# SDA381V7_B1.net
KiCad netlist of a schematic drawn in EAGLE
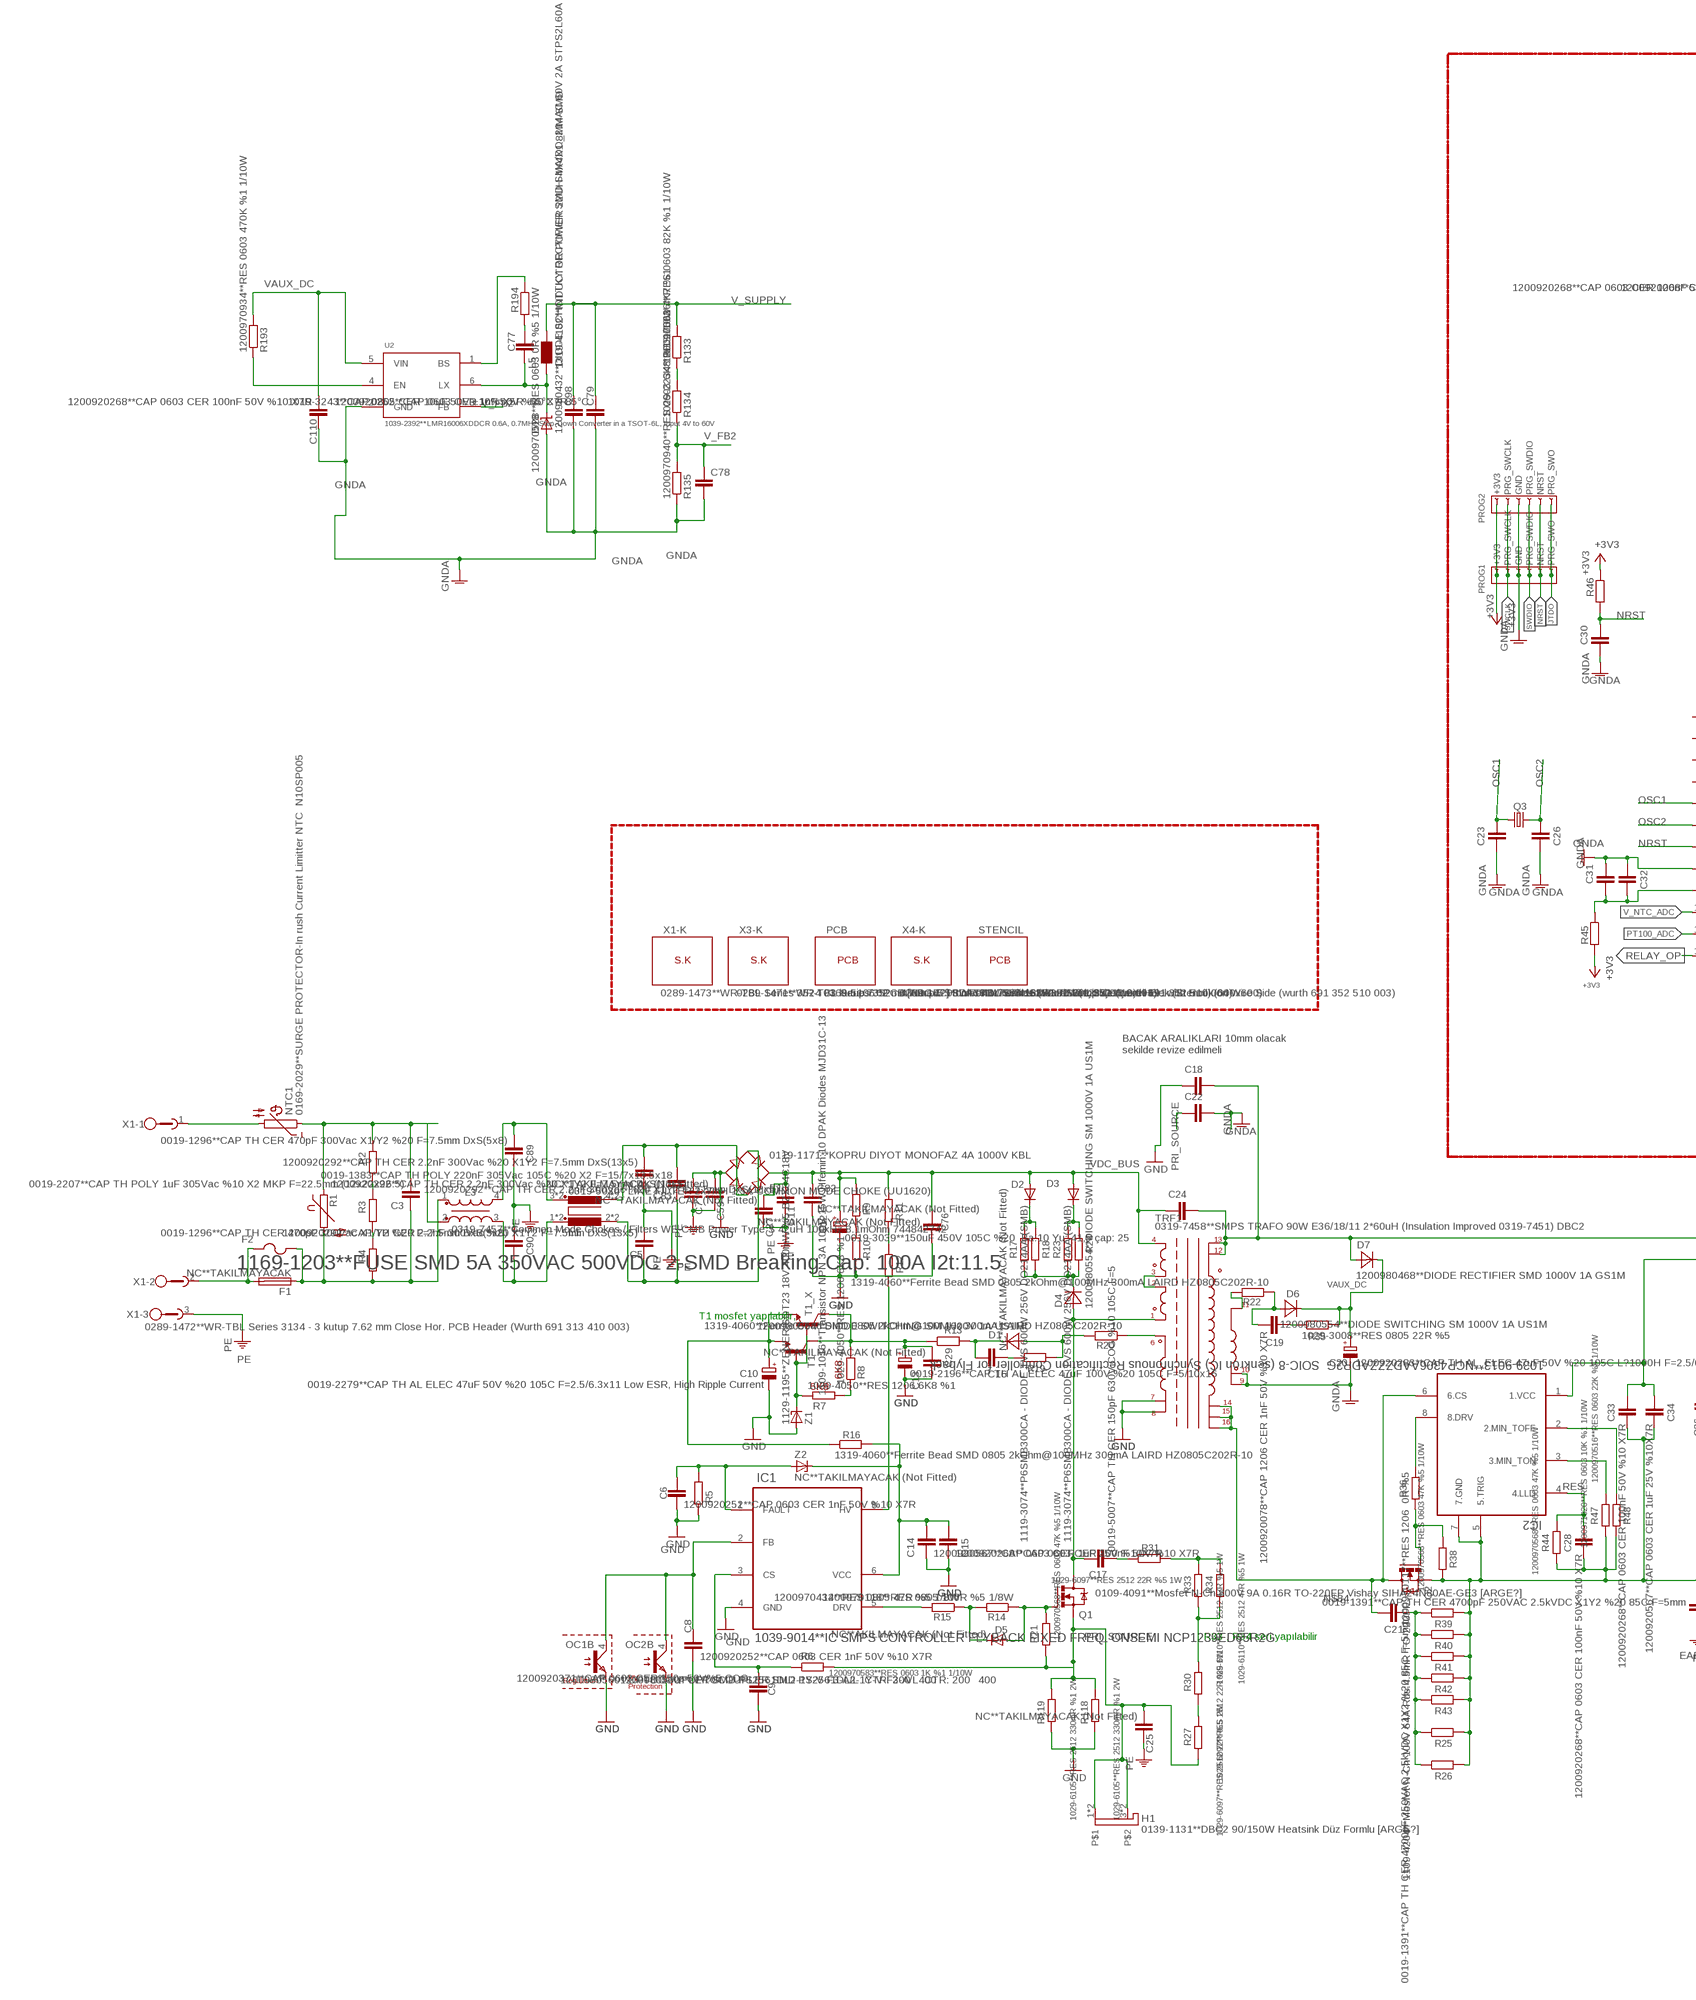
[diagram p0: schematic, sheet 1, part 1 of 2]
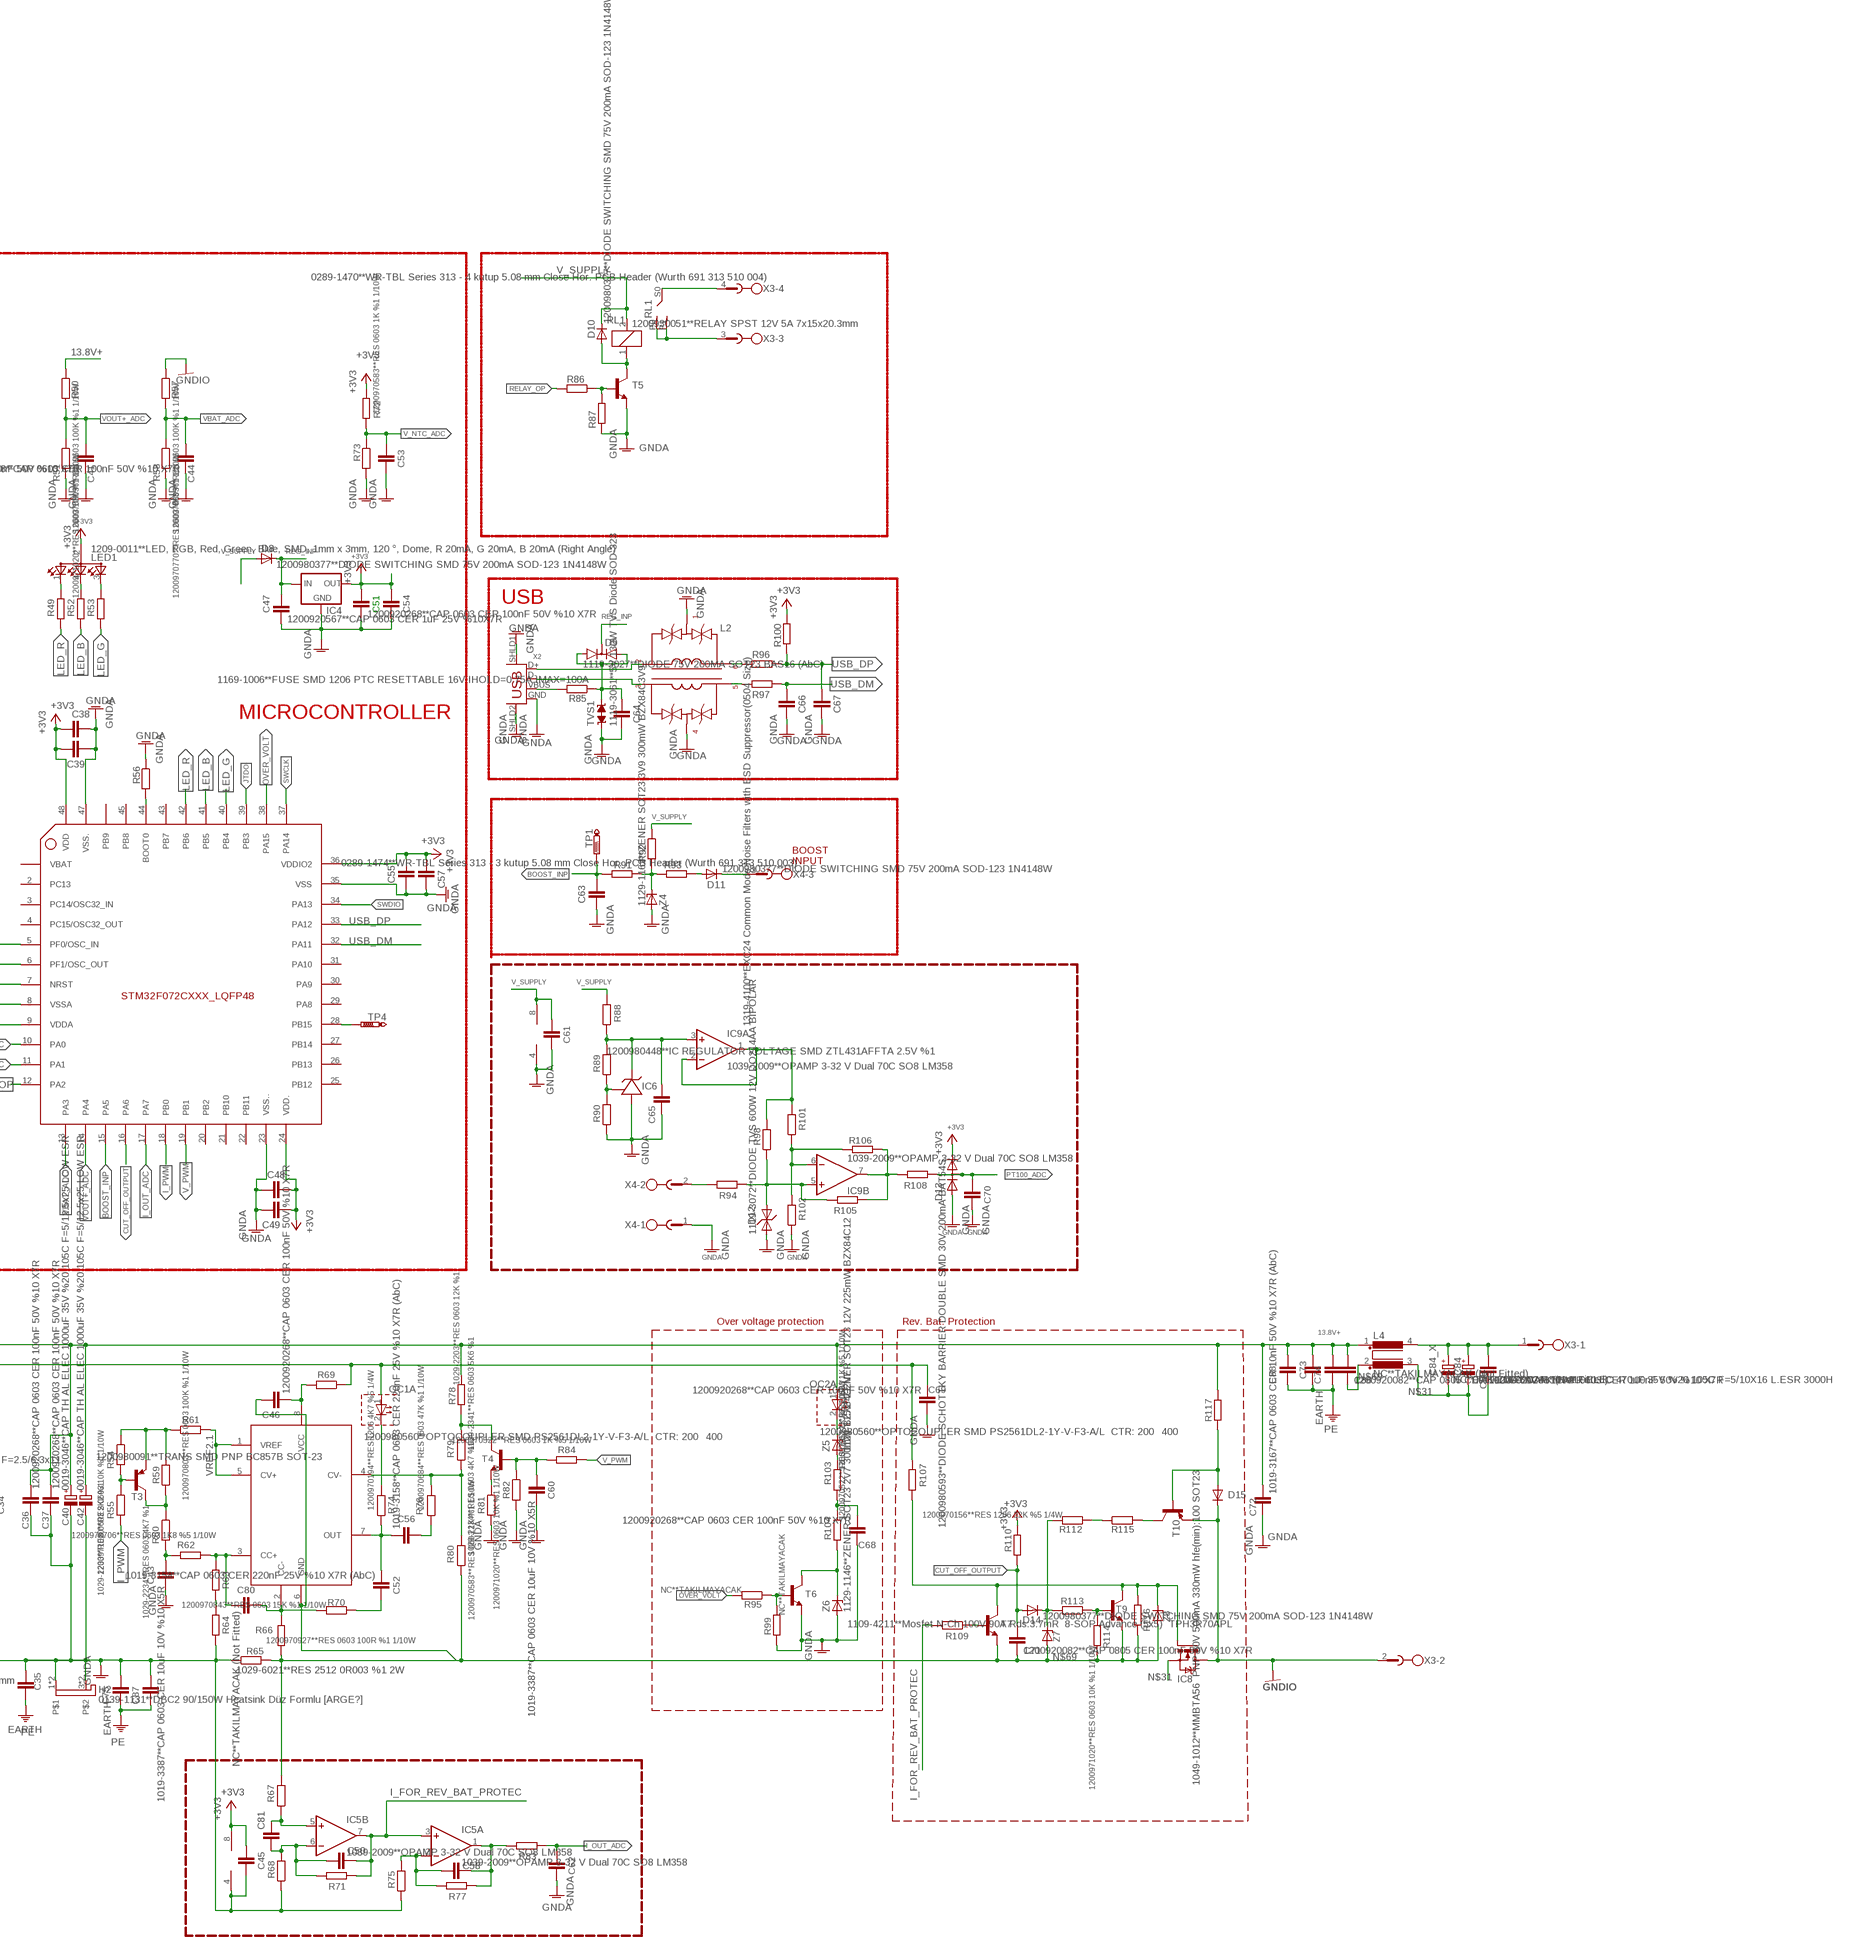
[diagram p1: schematic, sheet 1, part 2 of 2]

(export (version "E")
  (design (tool "Eeschema 10.0.6"))
  (components
    (comp (ref "B1")
      (value "0119-1171**KOPRU DIYOT MONOFAZ 4A 1000V KBL")
      (footprint "eagle-import:DıODE_BRIDGE_8A_DIK")
      (libsource (lib "eagle-import") (part "DıODE_BRIDGE_8A_DIK"))
    )
    (comp (ref "C3")
      (value "0019-2207**CAP TH POLY 1uF 305Vac %10 X2 MKP F=22.5mm (12x22x26.5)")
      (footprint "eagle-import:C275-113X316_&_C150-072X183_&_C225-113X268")
      (libsource (lib "eagle-import") (part "C275-113X316_&_C150-072X183_&_C225-113X268"))
    )
    (comp (ref "C4")
      (value "1200920292**CAP TH CER 2.2nF 300Vac %20 X1Y2 F=7.5mm DxS(13x5)")
      (footprint "eagle-import:C50-035X75")
      (libsource (lib "eagle-import") (part "C50-035X75"))
    )
    (comp (ref "C5")
      (value "1200920292**CAP TH CER 2.2nF 300Vac %20 X1Y2 F=7.5mm DxS(13x5)")
      (footprint "eagle-import:C50-035X75")
      (libsource (lib "eagle-import") (part "C50-035X75"))
    )
    (comp (ref "C6")
      (value "1200920252**CAP 0603 CER 1nF 50V %10 X7R")
      (footprint "eagle-import:C0603_ENKO")
      (libsource (lib "eagle-import") (part "C-EUC0603E"))
    )
    (comp (ref "C7")
      (value "1200920292**CAP TH CER 2.2nF 300Vac %20 X1Y2 F=7.5mm DxS(13x5)")
      (footprint "eagle-import:C50-035X75")
      (libsource (lib "eagle-import") (part "C50-035X75"))
    )
    (comp (ref "C8")
      (value "1200920252**CAP 0603 CER 1nF 50V %10 X7R")
      (footprint "eagle-import:C0603_ENKO")
      (libsource (lib "eagle-import") (part "C-EUC0603E"))
    )
    (comp (ref "C9")
      (value "1200920371**CAP 0603 CER 150p 50V%5 COG")
      (footprint "eagle-import:C0603_ENKO")
      (libsource (lib "eagle-import") (part "C-EUC0603E"))
    )
    (comp (ref "C10")
      (value "0019-2279**CAP TH AL ELEC 47uF 50V %20 105C F=2.5/6.3x11 Low ESR, High Ripple Current")
      (footprint "eagle-import:E2,5-7")
      (libsource (lib "eagle-import") (part "CPOL-EUE2.5-7"))
    )
    (comp (ref "C11")
      (value "1200920292**CAP TH CER 2.2nF 300Vac %20 X1Y2 F=7.5mm DxS(13x5)")
      (footprint "eagle-import:C50-035X75")
      (libsource (lib "eagle-import") (part "C50-035X75"))
    )
    (comp (ref "C12")
      (value "0019-3039**150uF 450V 105C %20 Ba:10 Yu: 41,5 çap: 25")
      (footprint "eagle-import:EB25D")
      (libsource (lib "eagle-import") (part "rcl_334_CPOL-EUE10-25"))
    )
    (comp (ref "C13")
      (value "0019-2196**CAP TH AL ELEC 47uF 100V %20 105C F=5/10x16")
      (footprint "eagle-import:E5-10,5")
      (libsource (lib "eagle-import") (part "CPOL-EUE5-10.5"))
    )
    (comp (ref "C14")
      (value "1200920567**CAP 0603 CER 1uF 25V %10X7R")
      (footprint "eagle-import:C0603_ENKO")
      (libsource (lib "eagle-import") (part "C-EUC0603E"))
    )
    (comp (ref "C15")
      (value "1200920268**CAP 0603 CER 100nF 50V %10 X7R")
      (footprint "eagle-import:C0603_ENKO")
      (libsource (lib "eagle-import") (part "C-EUC0603E"))
    )
    (comp (ref "C16")
      (value "NC**TAKILMAYACAK (Not Fitted)")
      (footprint "eagle-import:C1206_ENKO")
      (libsource (lib "eagle-import") (part "C-EUC1206E"))
    )
    (comp (ref "C17")
      (value "0019-5007**CAP TH CER 150pF 630V COG %10 105C F=5")
      (footprint "eagle-import:C075-32X103_C050-035X75")
      (libsource (lib "eagle-import") (part "C075-32X103/C050-035X75"))
    )
    (comp (ref "C18")
      (value "0019-1298**CAP TH CER 1nF 500Vac X1/Y1 %20 F=10mm DxS(5x9)")
      (footprint "eagle-import:C075-32X103_DEIF")
      (libsource (lib "eagle-import") (part "C075-32X103_DEIF"))
    )
    (comp (ref "C19")
      (value "1200920078**CAP 1206 CER 1nF 50V %10 X7R")
      (footprint "eagle-import:C1206_ENKO")
      (libsource (lib "eagle-import") (part "C-EUC1206E"))
    )
    (comp (ref "C20")
      (value "1200920283**CAP TH AL. ELEC 47uF 50V %20 105C L?1000H F=2.5/6.3x11")
      (footprint "eagle-import:E2,5-7")
      (libsource (lib "eagle-import") (part "rcl_334_CPOL-EUE2.5-7"))
    )
    (comp (ref "C21")
      (value "0019-1391**CAP TH CER 4700pF 250VAC 2.5kVDC X1Y2 %20 85C F=5mm")
      (footprint "eagle-import:C050-045X075")
      (libsource (lib "eagle-import") (part "C-EU050-045X075"))
    )
    (comp (ref "C22")
      (value "0019-1298**CAP TH CER 1nF 500Vac X1/Y1 %20 F=10mm DxS(5x9)")
      (footprint "eagle-import:C075-32X103_DEIF")
      (libsource (lib "eagle-import") (part "C075-32X103_DEIF"))
    )
    (comp (ref "C23")
      (value "1019-3352**CAP 0603 CER 22pF 50V %5 NPO")
      (footprint "eagle-import:C0603_ENKO")
      (libsource (lib "eagle-import") (part "C-EUC0603E"))
    )
    (comp (ref "C24")
      (value "0019-1299**CAP TH CER 2.2nF 500Vac X1/Y1 %20 F=10mm DxS(5x12)")
      (footprint "eagle-import:C075-32X103_DEIF")
      (libsource (lib "eagle-import") (part "C075-32X103_DEIF"))
    )
    (comp (ref "C25")
      (value "NC**TAKILMAYACAK (Not Fitted)")
      (footprint "eagle-import:C50-035X75")
      (libsource (lib "eagle-import") (part "C50-035X75"))
    )
    (comp (ref "C26")
      (value "1019-3352**CAP 0603 CER 22pF 50V %5 NPO")
      (footprint "eagle-import:C0603_ENKO")
      (libsource (lib "eagle-import") (part "C-EUC0603E"))
    )
    (comp (ref "C27")
      (value "NC**TAKILMAYACAK (Not Fitted)")
      (footprint "eagle-import:C50-035X75")
      (libsource (lib "eagle-import") (part "C50-035X75"))
    )
    (comp (ref "C28")
      (value "1200920268**CAP 0603 CER 100nF 50V %10 X7R")
      (footprint "eagle-import:C0603_ENKO")
      (libsource (lib "eagle-import") (part "C-EUC0603E"))
    )
    (comp (ref "C29")
      (value "NC**TAKILMAYACAK (Not Fitted)")
      (footprint "eagle-import:C1206_ENKO")
      (libsource (lib "eagle-import") (part "C-EUC1206E"))
    )
    (comp (ref "C30")
      (value "1200920268**CAP 0603 CER 100nF 50V %10 X7R")
      (footprint "eagle-import:C0603_ENKO")
      (libsource (lib "eagle-import") (part "C-EUC0603E"))
    )
    (comp (ref "C31")
      (value "1200920268**CAP 0603 CER 100nF 50V %10 X7R")
      (footprint "eagle-import:C0603_ENKO")
      (libsource (lib "eagle-import") (part "C-EUC0603E"))
    )
    (comp (ref "C32")
      (value "1019-3167**CAP 0603 CER 10nF 50V %10 X7R (AbC)")
      (footprint "eagle-import:C0603_ENKO")
      (libsource (lib "eagle-import") (part "C-EUC0603E"))
    )
    (comp (ref "C33")
      (value "1200920268**CAP 0603 CER 100nF 50V %10 X7R")
      (footprint "eagle-import:C0603_ENKO")
      (libsource (lib "eagle-import") (part "C-EUC0603E"))
    )
    (comp (ref "C34")
      (value "1200920567**CAP 0603 CER 1uF 25V %10X7R")
      (footprint "eagle-import:C0603_ENKO")
      (libsource (lib "eagle-import") (part "C-EUC0603E"))
    )
    (comp (ref "C35")
      (value "0019-1391**CAP TH CER 4700pF 250VAC 2.5kVDC X1Y2 %20 85C F=5mm")
      (footprint "eagle-import:C050-045X075")
      (libsource (lib "eagle-import") (part "C-EU050-045X075"))
    )
    (comp (ref "C36")
      (value "1200920268**CAP 0603 CER 100nF 50V %10 X7R")
      (footprint "eagle-import:C0603_ENKO")
      (libsource (lib "eagle-import") (part "C-EUC0603E"))
    )
    (comp (ref "C37")
      (value "1200920268**CAP 0603 CER 100nF 50V %10 X7R")
      (footprint "eagle-import:C0603_ENKO")
      (libsource (lib "eagle-import") (part "C-EUC0603E"))
    )
    (comp (ref "C38")
      (value "1200920268**CAP 0603 CER 100nF 50V %10 X7R")
      (footprint "eagle-import:C0603_ENKO")
      (libsource (lib "eagle-import") (part "C-EUC0603E"))
    )
    (comp (ref "C39")
      (value "1019-3167**CAP 0603 CER 10nF 50V %10 X7R (AbC)")
      (footprint "eagle-import:C0603_ENKO")
      (libsource (lib "eagle-import") (part "C-EUC0603E"))
    )
    (comp (ref "C40")
      (value "0019-3046**CAP TH AL ELEC 1000uF 35V %20 105C F=5/12.5x25 LOW ESR")
      (footprint "eagle-import:E5-13_E7,5-16")
      (libsource (lib "eagle-import") (part "E5-13/E7,5-16"))
    )
    (comp (ref "C41")
      (value "1200920268**CAP 0603 CER 100nF 50V %10 X7R")
      (footprint "eagle-import:C0603_ENKO")
      (libsource (lib "eagle-import") (part "C-EUC0603E"))
    )
    (comp (ref "C42")
      (value "0019-3046**CAP TH AL ELEC 1000uF 35V %20 105C F=5/12.5x25 LOW ESR")
      (footprint "eagle-import:E5-13")
      (libsource (lib "eagle-import") (part "CPOL-EUE5-13"))
    )
    (comp (ref "C43")
      (value "1019-3387**CAP 0603 CER 10uF 10V %10 X5R")
      (footprint "eagle-import:C0603_ENKO")
      (libsource (lib "eagle-import") (part "C-EUC0603E"))
    )
    (comp (ref "C44")
      (value "1200920268**CAP 0603 CER 100nF 50V %10 X7R")
      (footprint "eagle-import:C0603_ENKO")
      (libsource (lib "eagle-import") (part "C-EUC0603E"))
    )
    (comp (ref "C45")
      (value "1200920268**CAP 0603 CER 100nF 50V %10 X7R")
      (footprint "eagle-import:C0603_ENKO")
      (libsource (lib "eagle-import") (part "C-EUC0603E"))
    )
    (comp (ref "C46")
      (value "1200920268**CAP 0603 CER 100nF 50V %10 X7R")
      (footprint "eagle-import:C0603_ENKO")
      (libsource (lib "eagle-import") (part "C-EUC0603E"))
    )
    (comp (ref "C47")
      (value "1200920567**CAP 0603 CER 1uF 25V %10X7R")
      (footprint "eagle-import:C0603_ENKO")
      (libsource (lib "eagle-import") (part "C-EUC0603E"))
    )
    (comp (ref "C48")
      (value "1019-3167**CAP 0603 CER 10nF 50V %10 X7R (AbC)")
      (footprint "eagle-import:C0603_ENKO")
      (libsource (lib "eagle-import") (part "C-EUC0603E"))
    )
    (comp (ref "C49")
      (value "1200920268**CAP 0603 CER 100nF 50V %10 X7R")
      (footprint "eagle-import:C0603_ENKO")
      (libsource (lib "eagle-import") (part "C-EUC0603E"))
    )
    (comp (ref "C50")
      (value "NC**TAKILMAYACAK (Not Fitted)")
      (footprint "eagle-import:C0603_ENKO")
      (libsource (lib "eagle-import") (part "C-EUC0603E"))
    )
    (comp (ref "C51")
      (value "1200920268**CAP 0603 CER 100nF 50V %10 X7R")
      (footprint "eagle-import:C0603_ENKO")
      (libsource (lib "eagle-import") (part "C-EUC0603E"))
    )
    (comp (ref "C52")
      (value "1019-3158**CAP 0603 CER 220nF 25V %10 X7R (AbC)")
      (footprint "eagle-import:C0603_ENKO")
      (libsource (lib "eagle-import") (part "C-EUC0603E"))
    )
    (comp (ref "C53")
      (value "1200920268**CAP 0603 CER 100nF 50V %10 X7R")
      (footprint "eagle-import:C0603_ENKO")
      (libsource (lib "eagle-import") (part "C-EUC0603E"))
    )
    (comp (ref "C54")
      (value "1019-3301**CAP 0805 47uF 6.3V %20 X5R")
      (footprint "eagle-import:C0805_ENKO")
      (libsource (lib "eagle-import") (part "C-EUC0805E"))
    )
    (comp (ref "C55")
      (value "1019-3167**CAP 0603 CER 10nF 50V %10 X7R (AbC)")
      (footprint "eagle-import:C0603_ENKO")
      (libsource (lib "eagle-import") (part "C-EUC0603E"))
    )
    (comp (ref "C56")
      (value "1019-3158**CAP 0603 CER 220nF 25V %10 X7R (AbC)")
      (footprint "eagle-import:C0603_ENKO")
      (libsource (lib "eagle-import") (part "C-EUC0603E"))
    )
    (comp (ref "C57")
      (value "1200920268**CAP 0603 CER 100nF 50V %10 X7R")
      (footprint "eagle-import:C0603_ENKO")
      (libsource (lib "eagle-import") (part "C-EUC0603E"))
    )
    (comp (ref "C58")
      (value "1200920371**CAP 0603 CER 150p 50V%5 COG")
      (footprint "eagle-import:C0603_ENKO")
      (libsource (lib "eagle-import") (part "C-EUC0603E"))
    )
    (comp (ref "C59")
      (value "NC**TAKILMAYACAK (Not Fitted)")
      (footprint "eagle-import:C50-035X75")
      (libsource (lib "eagle-import") (part "C50-035X75"))
    )
    (comp (ref "C60")
      (value "1019-3387**CAP 0603 CER 10uF 10V %10 X5R")
      (footprint "eagle-import:C0603_ENKO")
      (libsource (lib "eagle-import") (part "C-EUC0603E"))
    )
    (comp (ref "C61")
      (value "1200920268**CAP 0603 CER 100nF 50V %10 X7R")
      (footprint "eagle-import:C0603_ENKO")
      (libsource (lib "eagle-import") (part "C-EUC0603E"))
    )
    (comp (ref "C62")
      (value "1200920268**CAP 0603 CER 100nF 50V %10 X7R")
      (footprint "eagle-import:C0603_ENKO")
      (libsource (lib "eagle-import") (part "C-EUC0603E"))
    )
    (comp (ref "C63")
      (value "1019-3167**CAP 0603 CER 10nF 50V %10 X7R (AbC)")
      (footprint "eagle-import:C0603_ENKO")
      (libsource (lib "eagle-import") (part "C-EUC0603E"))
    )
    (comp (ref "C64")
      (value "1200920268**CAP 0603 CER 100nF 50V %10 X7R")
      (footprint "eagle-import:C0603_ENKO")
      (libsource (lib "eagle-import") (part "C-EUC0603E"))
    )
    (comp (ref "C65")
      (value "1200920268**CAP 0603 CER 100nF 50V %10 X7R")
      (footprint "eagle-import:C0603_ENKO")
      (libsource (lib "eagle-import") (part "C-EUC0603E"))
    )
    (comp (ref "C66")
      (value "1019-3381**CAP 0603 CER 33pf 50V %5 NPO(COG)")
      (footprint "eagle-import:C0603_ENKO")
      (libsource (lib "eagle-import") (part "C-EUC0603E"))
    )
    (comp (ref "C67")
      (value "1019-3381**CAP 0603 CER 33pf 50V %5 NPO(COG)")
      (footprint "eagle-import:C0603_ENKO")
      (libsource (lib "eagle-import") (part "C-EUC0603E"))
    )
    (comp (ref "C68")
      (value "1200920268**CAP 0603 CER 100nF 50V %10 X7R")
      (footprint "eagle-import:C0603_ENKO")
      (libsource (lib "eagle-import") (part "C-EUC0603E"))
    )
    (comp (ref "C69")
      (value "1200920268**CAP 0603 CER 100nF 50V %10 X7R")
      (footprint "eagle-import:C0603_ENKO")
      (libsource (lib "eagle-import") (part "C-EUC0603E"))
    )
    (comp (ref "C70")
      (value "1200920268**CAP 0603 CER 100nF 50V %10 X7R")
      (footprint "eagle-import:C0603_ENKO")
      (libsource (lib "eagle-import") (part "C-EUC0603E"))
    )
    (comp (ref "C71")
      (value "1200920082**CAP 0805 CER 100nF 50V %10 X7R")
      (footprint "eagle-import:C0805_ENKO")
      (libsource (lib "eagle-import") (part "C-EUC0805E"))
    )
    (comp (ref "C72")
      (value "1019-3167**CAP 0603 CER 10nF 50V %10 X7R (AbC)")
      (footprint "eagle-import:C0603_ENKO")
      (libsource (lib "eagle-import") (part "C-EUC0603E"))
    )
    (comp (ref "C73")
      (value "0019-1391**CAP TH CER 4700pF 250VAC 2.5kVDC X1Y2 %20 85C F=5mm")
      (footprint "eagle-import:C050-035X075")
      (libsource (lib "eagle-import") (part "C-EU050-035X075"))
    )
    (comp (ref "C74")
      (value "0019-1391**CAP TH CER 4700pF 250VAC 2.5kVDC X1Y2 %20 85C F=5mm")
      (footprint "eagle-import:C075-32X103_DEIF")
      (libsource (lib "eagle-import") (part "C075-32X103_DEIF"))
    )
    (comp (ref "C75")
      (value "0019-1391**CAP TH CER 4700pF 250VAC 2.5kVDC X1Y2 %20 85C F=5mm")
      (footprint "eagle-import:C075-32X103_DEIF")
      (libsource (lib "eagle-import") (part "C075-32X103_DEIF"))
    )
    (comp (ref "C76")
      (value "NC**TAKILMAYACAK (Not Fitted)")
      (footprint "eagle-import:C065-052X106")
      (libsource (lib "eagle-import") (part "C065-052X106"))
    )
    (comp (ref "C77")
      (value "1200920268**CAP 0603 CER 100nF 50V %10 X7R")
      (footprint "eagle-import:C0603_ENKO")
      (libsource (lib "eagle-import") (part "C-EUC0603E"))
    )
    (comp (ref "C78")
      (value "1019-3352**CAP 0603 CER 22pF 50V %5 NPO")
      (footprint "eagle-import:C0603_ENKO")
      (libsource (lib "eagle-import") (part "C-EUC0603E"))
    )
    (comp (ref "C79")
      (value "1019-3243**CAP 0805 CER 10uF 50V ±10% X5R -55°C ~ 85°C")
      (footprint "eagle-import:C0805_ENKO")
      (libsource (lib "eagle-import") (part "C-EUC0805E"))
    )
    (comp (ref "C80")
      (value "NC**TAKILMAYACAK (Not Fitted)")
      (footprint "eagle-import:C0603_ENKO")
      (libsource (lib "eagle-import") (part "C-EUC0603E"))
    )
    (comp (ref "C81")
      (value "NC**TAKILMAYACAK (Not Fitted)")
      (footprint "eagle-import:C0603_ENKO")
      (libsource (lib "eagle-import") (part "C-EUC0603E"))
    )
    (comp (ref "C82")
      (value "NC**TAKILMAYACAK (Not Fitted)")
      (footprint "eagle-import:C150-091X182")
      (libsource (lib "eagle-import") (part "C-EU150-091X182"))
    )
    (comp (ref "C83")
      (value "0019-1383**CAP TH POLY 220nF 305Vac 105C %20 X2 F=15/7x13.5x18")
      (footprint "eagle-import:C150-091X182_C225-108X268")
      (libsource (lib "eagle-import") (part "C150-091X182_C225-108X268"))
    )
    (comp (ref "C84")
      (value "0019-7012**CAP TH AL. ELEC 470uF 35V %20 105C F=5/10X16 L.ESR 3000H")
      (footprint "eagle-import:E5-10,5")
      (libsource (lib "eagle-import") (part "CPOL-EUE5-10.5"))
    )
    (comp (ref "C84_X")
      (value "NC**TAKILMAYACAK (Not Fitted)")
      (footprint "eagle-import:E2,5-7")
      (libsource (lib "eagle-import") (part "CPOL-EUE2.5-7"))
    )
    (comp (ref "C85")
      (value "1200920268**CAP 0603 CER 100nF 50V %10 X7R")
      (footprint "eagle-import:C0603_ENKO")
      (libsource (lib "eagle-import") (part "C-EUC0603E"))
    )
    (comp (ref "C86")
      (value "1200920082**CAP 0805 CER 100nF 50V %10 X7R")
      (footprint "eagle-import:C0805_ENKO")
      (libsource (lib "eagle-import") (part "C-EUC0805E"))
    )
    (comp (ref "C87")
      (value "0019-3044**CAP TH CER 1nF 400VAC X1 %20 85C F=5 veya F=7.5 D=6.5")
      (footprint "eagle-import:C075-32X103_DEIF")
      (libsource (lib "eagle-import") (part "C075-32X103_DEIF"))
    )
    (comp (ref "C88")
      (value "0019-3044**CAP TH CER 1nF 400VAC X1 %20 85C F=5 veya F=7.5 D=6.5")
      (footprint "eagle-import:C075-32X103_DEIF")
      (libsource (lib "eagle-import") (part "C075-32X103_DEIF"))
    )
    (comp (ref "C89")
      (value "0019-1296**CAP TH CER 470pF 300Vac X1/Y2 %20 F=7.5mm DxS(5x8)")
      (footprint "eagle-import:C075-32X103_C050-035X75")
      (libsource (lib "eagle-import") (part "C075-32X103/C050-035X75"))
    )
    (comp (ref "C90")
      (value "0019-1296**CAP TH CER 470pF 300Vac X1/Y2 %20 F=7.5mm DxS(5x8)")
      (footprint "eagle-import:C075-32X103_C050-035X75")
      (libsource (lib "eagle-import") (part "C075-32X103/C050-035X75"))
    )
    (comp (ref "C98")
      (value "1200920252**CAP 0603 CER 1nF 50V %10 X7R")
      (footprint "eagle-import:C0603_ENKO")
      (libsource (lib "eagle-import") (part "C-EUC0603E"))
    )
    (comp (ref "C110")
      (value "1200920268**CAP 0603 CER 100nF 50V %10 X7R")
      (footprint "eagle-import:C0603_ENKO")
      (libsource (lib "eagle-import") (part "C-EUC0603E"))
    )
    (comp (ref "D1")
      (value "1200980554**DIODE SWITCHING SM 1000V 1A US1M")
      (footprint "eagle-import:M7_DC_DIYOT")
      (libsource (lib "eagle-import") (part "M7_DC_DIYOT"))
    )
    (comp (ref "D2")
      (value "1119-3074**P6SMB300CA - DIODE TVS 600W 256V DO214AA (SMB)")
      (footprint "eagle-import:SMB")
      (libsource (lib "eagle-import") (part "DIODE-SMB"))
    )
    (comp (ref "D3")
      (value "1119-3074**P6SMB300CA - DIODE TVS 600W 256V DO214AA (SMB)")
      (footprint "eagle-import:SMB")
      (libsource (lib "eagle-import") (part "DIODE-SMB"))
    )
    (comp (ref "D4")
      (value "1200980554**DIODE SWITCHING SM 1000V 1A US1M")
      (footprint "eagle-import:M7_DC_DIYOT")
      (libsource (lib "eagle-import") (part "M7_DC_DIYOT"))
    )
    (comp (ref "D5")
      (value "NC**AKILMAYACAK (Not Fitted)")
      (footprint "eagle-import:SOD123")
      (libsource (lib "eagle-import") (part "DIODE-SOD123"))
    )
    (comp (ref "D6")
      (value "1200980554**DIODE SWITCHING SM 1000V 1A US1M")
      (footprint "eagle-import:M7_DC_DIYOT")
      (libsource (lib "eagle-import") (part "M7_DC_DIYOT"))
    )
    (comp (ref "D7")
      (value "1200980468**DIODE RECTIFIER SMD 1000V 1A GS1M")
      (footprint "eagle-import:M7_DC_DIYOT")
      (libsource (lib "eagle-import") (part "M7_DC_DIYOT"))
    )
    (comp (ref "D8")
      (value "1200980377**DIODE SWITCHING SMD 75V 200mA SOD-123 1N4148W")
      (footprint "eagle-import:SOD123")
      (libsource (lib "eagle-import") (part "DIODE-SOD123"))
    )
    (comp (ref "D9")
      (value "1119-3027**DIODE 75V 200MA SOT23 BAS16 (AbC)")
      (footprint "eagle-import:SOT23")
      (libsource (lib "eagle-import") (part "DIODE-2AC|CASOT23"))
    )
    (comp (ref "D10")
      (value "1200980377**DIODE SWITCHING SMD 75V 200mA SOD-123 1N4148W")
      (footprint "eagle-import:SOD123")
      (libsource (lib "eagle-import") (part "DIODE-SOD123"))
    )
    (comp (ref "D11")
      (value "1200980377**DIODE SWITCHING SMD 75V 200mA SOD-123 1N4148W")
      (footprint "eagle-import:SOD123")
      (libsource (lib "eagle-import") (part "DIODE-SOD123"))
    )
    (comp (ref "D12")
      (value "1119-3072**DIODE TVS 600W 12V DO214AA BIPOLAR")
      (footprint "eagle-import:TRANSIL_SMB")
      (libsource (lib "eagle-import") (part "TRANSIL_SMB"))
    )
    (comp (ref "D13")
      (value "1200980593**DIODE SCHOTTKY BARRIER DOUBLE SMD 30V 200mA BAT54S")
      (footprint "eagle-import:SOT23")
      (libsource (lib "eagle-import") (part "BAV199"))
    )
    (comp (ref "D14")
      (value "1200980377**DIODE SWITCHING SMD 75V 200mA SOD-123 1N4148W")
      (footprint "eagle-import:SOD123")
      (libsource (lib "eagle-import") (part "DIODE-SOD123"))
    )
    (comp (ref "D15")
      (value "1200980377**DIODE SWITCHING SMD 75V 200mA SOD-123 1N4148W")
      (footprint "eagle-import:SOD123")
      (libsource (lib "eagle-import") (part "DIODE-SOD123"))
    )
    (comp (ref "D18")
      (value "1200980432**DIODE SCHOTTKY RECTIFIER SMD SMA/DO_214AC 60V 2A STPS2L60A")
      (footprint "eagle-import:SMA")
      (libsource (lib "eagle-import") (part "SD-SMA"))
    )
    (comp (ref "F1")
      (value "NC**TAKILMAYACAK")
      (footprint "eagle-import:SENS_FUSE")
      (libsource (lib "eagle-import") (part "SENS_FUSE"))
    )
    (comp (ref "F2")
      (value "1169-1203**FUSE SMD 5A 350VAC 500VDC 2-SMD Breaking Cap: 100A I2t:11.5")
      (footprint "eagle-import:FUSE_1350HV_EAT")
      (fields
        (field (name "MANUFACTURER_PART_NUMBER") "TR-1350HV5-R")
        (field (name "COPYRIGHT") "Copyright (C) 2025 Ultra Librarian. All rights reserved.")
      )
      (libsource (lib "eagle-import") (part "TR-1350HV5-RFUSE_1350HV_EAT"))
    )
    (comp (ref "H1")
      (value "0139-1131**DBC2 90/150W Heatsink Düz Formlu [ARGE?]")
      (footprint "eagle-import:DEIF_SOGUTUCU_2")
      (libsource (lib "eagle-import") (part "DEIF_SOGUTUCU_2"))
    )
    (comp (ref "H2")
      (value "0139-1131**DBC2 90/150W Heatsink Düz Formlu [ARGE?]")
      (footprint "eagle-import:DEIF_SOGUTUCU_2")
      (libsource (lib "eagle-import") (part "DEIF_SOGUTUCU_2"))
    )
    (comp (ref "IC1")
      (value "1039-9014**IC SMPS CONTROLLER FLYBACK FIXED FREQ. ONSEMI NCP1239ED65R2G")
      (footprint "eagle-import:NCP1239_SMPS_IC")
      (libsource (lib "eagle-import") (part "NCP1239_SMPS_IC"))
    )
    (comp (ref "IC2")
      (value "1039-9013**NCP4306AADZZZADR2G SOIC-8 (senkron IC) Synchronous Rectification Controller for Flyback")
      (footprint "eagle-import:NCP4306")
      (libsource (lib "eagle-import") (part "NCP4306"))
    )
    (comp (ref "IC3")
      (value "1039-2224**TSM1011ID SO-8 Constant Voltage and Constant Current Controller")
      (footprint "eagle-import:SO-8")
      (libsource (lib "eagle-import") (part "TSM1011"))
    )
    (comp (ref "IC4")
      (value "1039-3003**Voltage Regulator SOT-89 3.3V Diodes AP2204RA-3.3TRG1")
      (footprint "eagle-import:SOT89")
      (libsource (lib "eagle-import") (part "S-812XSGUP"))
    )
    (comp (ref "IC5")
      (value "1039-2009**OPAMP 3-32 V Dual 70C SO8 LM358")
      (footprint "eagle-import:SO08")
      (libsource (lib "eagle-import") (part "LM358D"))
    )
    (comp (ref "IC6")
      (value "1200980448**IC REGULATOR VOLTAGE SMD ZTL431AFFTA 2.5V %1")
      (footprint "eagle-import:TL431_SOT23F")
      (libsource (lib "eagle-import") (part "TL431_SOT23F"))
    )
    (comp (ref "IC8")
      (value "1109-4211**Mosfet N-Ch 100V 90A Rds:3.7mR 8-SOP Advance (5x5) TPH3R70APL")
      (footprint "eagle-import:TPH6R30ANL")
      (libsource (lib "eagle-import") (part "TPH6R30ANL"))
    )
    (comp (ref "IC9")
      (value "1039-2009**OPAMP 3-32 V Dual 70C SO8 LM358")
      (footprint "eagle-import:SO08")
      (libsource (lib "eagle-import") (part "LM358D"))
    )
    (comp (ref "L1")
      (value "0319-5030**LINE FILTER 2x7mH 1,5A COMMON MODE CHOKE (UU1620)")
      (footprint "eagle-import:UU1620_&_FWCMET24V")
      (libsource (lib "eagle-import") (part "UU1620_&_FWCMET24V"))
    )
    (comp (ref "L2")
      (value "1319-4100**EXC24 Common Mode Noise Filters with ESD Suppressor(0504 Size)")
      (footprint "eagle-import:EXC24CS_COMMON_MODE")
      (libsource (lib "eagle-import") (part "EXC24CS_COMMON_MODE"))
    )
    (comp (ref "L3")
      (value "0319-7457**Common Mode Chokes / Filters WE-CMB Power Type S 42uH 100kHz 8.1mOhm 744842742")
      (footprint "eagle-import:WE-CMB_NIZN_S")
      (libsource (lib "eagle-import") (part "WE-CMB_NIZN_S_744842742"))
    )
    (comp (ref "L4")
      (value "NC**TAKILMAYACAK (Not Fitted)")
      (footprint "eagle-import:CM2021Y330R-10")
      (libsource (lib "eagle-import") (part "CM2021Y330R-10"))
    )
    (comp (ref "L5")
      (value "1319-4102**INDUCTOR POWER 22UH 4X4X1.8MM SMD")
      (footprint "eagle-import:WE-PD2_5MM")
      (libsource (lib "eagle-import") (part "WE-PD2WE_PD2_5MM"))
    )
    (comp (ref "LED1")
      (value "1209-0011**LED, RGB, Red, Green, Blue, SMD, 1mm x 3mm, 120 °, Dome, R 20mA, G 20mA, B 20mA (Right Angle)")
      (footprint "eagle-import:KPFA-3010RGBC-11")
      (libsource (lib "eagle-import") (part "KPFA-3010RGBC-11"))
    )
    (comp (ref "NTC1")
      (value "0169-2029**SURGE PROTECTOR-In rush Current Limitter NTC N10SP005")
      (footprint "eagle-import:NTC_15R_2A_&_N15SP005-5")
      (libsource (lib "eagle-import") (part "NTC_15R_2A_&_N15SP005-5"))
    )
    (comp (ref "OC1")
      (value "1200980560**OPTOCOUPLER SMD PS2561DL2-1Y-V-F3-A/L  CTR: 200˜400")
      (footprint "eagle-import:PS2561DL2-1_OPTO1")
      (libsource (lib "eagle-import") (part "PS2561DL2-1_OPTO1"))
    )
    (comp (ref "OC2")
      (value "1200980560**OPTOCOUPLER SMD PS2561DL2-1Y-V-F3-A/L  CTR: 200˜400")
      (footprint "eagle-import:PS2561DL2-1_OPTO1")
      (libsource (lib "eagle-import") (part "PS2561DL2-1_OPTO1"))
    )
    (comp (ref "PCB")
      (value "0369-5106**PCB [ARGE?] SDA381V7CF416M3HFS2(123x113.2)")
      (footprint "eagle-import:PCB")
      (libsource (lib "eagle-import") (part "PCB"))
    )
    (comp (ref "PROG1")
      (value "NC**TAKILMAYACAK (Not Fitted)")
      (footprint "eagle-import:PROG_6PIN")
      (libsource (lib "eagle-import") (part "PROG_6PIN"))
    )
    (comp (ref "PROG2")
      (value "NC**TAKILMAYACAK (Not Fitted)")
      (footprint "eagle-import:PROG_6PIN")
      (libsource (lib "eagle-import") (part "PROG_6PIN"))
    )
    (comp (ref "Q1")
      (value "0109-4091**Mosfet N-Ch 800V 9A 0.16R TO-220FP Vishay SIHA24N80AE-GE3 [ARGE?]")
      (footprint "eagle-import:TO220BV")
      (libsource (lib "eagle-import") (part "STP5NA50"))
    )
    (comp (ref "Q2")
      (value "1109-4204**Mosfet N-Ch 100V 64A Rds:4.5mR TO-220FP")
      (footprint "eagle-import:TO220BV")
      (libsource (lib "eagle-import") (part "STP5NA50"))
    )
    (comp (ref "Q3")
      (value "1149-0006**HC49S SMD KRISTAL 8MHZ -40+85 20PF 50PPM FAT Y3MM")
      (footprint "eagle-import:HC49UP")
      (libsource (lib "eagle-import") (part "CRYSTALHC49UP"))
    )
    (comp (ref "R1")
      (value "0169-2013**Varistor 20mm 300V")
      (footprint "eagle-import:S20K40")
      (libsource (lib "eagle-import") (part "S20K40"))
    )
    (comp (ref "R2")
      (value "1200970587**RES 1206 470K %5 1/4W")
      (footprint "eagle-import:R1206_ENKO")
      (libsource (lib "eagle-import") (part "R-EU_R1206E"))
    )
    (comp (ref "R3")
      (value "1200970587**RES 1206 470K %5 1/4W")
      (footprint "eagle-import:R1206_ENKO")
      (libsource (lib "eagle-import") (part "R-EU_R1206E"))
    )
    (comp (ref "R4")
      (value "1200970587**RES 1206 470K %5 1/4W")
      (footprint "eagle-import:R1206_ENKO")
      (libsource (lib "eagle-import") (part "R-EU_R1206E"))
    )
    (comp (ref "R5")
      (value "1200970687**RES 0603 56K %1 1/10W")
      (footprint "eagle-import:R0603_ENKO")
      (libsource (lib "eagle-import") (part "R-EU_R0603E"))
    )
    (comp (ref "R6")
      (value "1200970583**RES 0603 1K %1 1/10W")
      (footprint "eagle-import:R0603_ENKO")
      (libsource (lib "eagle-import") (part "R-EU_R0603E"))
    )
    (comp (ref "R7")
      (value "1029-4050**RES 1206 6K8 %1")
      (footprint "eagle-import:R1206_ENKO")
      (libsource (lib "eagle-import") (part "R-EU_R1206E"))
    )
    (comp (ref "R8")
      (value "1029-4050**RES 1206 6K8 %1")
      (footprint "eagle-import:R1206_ENKO")
      (libsource (lib "eagle-import") (part "R-EU_R1206E"))
    )
    (comp (ref "R9")
      (value "1200970179**RES 1206 330K %5 1/4W")
      (footprint "eagle-import:R1206_ENKO")
      (libsource (lib "eagle-import") (part "R-EU_R1206E"))
    )
    (comp (ref "R10")
      (value "1200970179**RES 1206 330K %5 1/4W")
      (footprint "eagle-import:R1206_ENKO")
      (libsource (lib "eagle-import") (part "R-EU_R1206E"))
    )
    (comp (ref "R11")
      (value "1200970154**RES 1206 2K2 %5 1/4W")
      (footprint "eagle-import:R1206_ENKO")
      (libsource (lib "eagle-import") (part "R-EU_R1206E"))
    )
    (comp (ref "R12")
      (value "1200970154**RES 1206 2K2 %5 1/4W")
      (footprint "eagle-import:R1206_ENKO")
      (libsource (lib "eagle-import") (part "R-EU_R1206E"))
    )
    (comp (ref "R13")
      (value "1029-3146**RES 1206 7R68 %1")
      (footprint "eagle-import:R1206_ENKO")
      (libsource (lib "eagle-import") (part "R-EU_R1206E"))
    )
    (comp (ref "R14")
      (value "1200970118**RES 0805 100R %5 1/8W")
      (footprint "eagle-import:R0805_ENKO")
      (libsource (lib "eagle-import") (part "R-EU_R0805E"))
    )
    (comp (ref "R15")
      (value "1200970434**RES 0805 47R %5 1/8W")
      (footprint "eagle-import:R0805_ENKO")
      (libsource (lib "eagle-import") (part "R-EU_R0805E"))
    )
    (comp (ref "R16")
      (value "1319-4060**Ferrite Bead SMD 0805 2kOhm@100MHz 300mA LAIRD HZ0805C202R-10")
      (footprint "eagle-import:R0805_ENKO")
      (libsource (lib "eagle-import") (part "R-EU_R0805E"))
    )
    (comp (ref "R17")
      (value "1029-3146**RES 1206 7R68 %1")
      (footprint "eagle-import:R1206_ENKO")
      (libsource (lib "eagle-import") (part "R-EU_R1206E"))
    )
    (comp (ref "R18")
      (value "1029-3146**RES 1206 7R68 %1")
      (footprint "eagle-import:R1206_ENKO")
      (libsource (lib "eagle-import") (part "R-EU_R1206E"))
    )
    (comp (ref "R19")
      (value "NC**TAKILMAYACAK (Not Fitted)")
      (footprint "eagle-import:R1206_ENKO")
      (libsource (lib "eagle-import") (part "R-EU_R1206E"))
    )
    (comp (ref "R20")
      (value "1319-4060**Ferrite Bead SMD 0805 2kOhm@100MHz 300mA LAIRD HZ0805C202R-10")
      (footprint "eagle-import:R0805_ENKO")
      (libsource (lib "eagle-import") (part "R-EU_R0805E"))
    )
    (comp (ref "R21")
      (value "1200970568**RES 0603 47K %5 1/10W")
      (footprint "eagle-import:R0603_ENKO")
      (libsource (lib "eagle-import") (part "R-EU_R0603E"))
    )
    (comp (ref "R22")
      (value "1319-4060**Ferrite Bead SMD 0805 2kOhm@100MHz 300mA LAIRD HZ0805C202R-10")
      (footprint "eagle-import:R0805_ENKO")
      (libsource (lib "eagle-import") (part "R-EU_R0805E"))
    )
    (comp (ref "R23")
      (value "1029-3146**RES 1206 7R68 %1")
      (footprint "eagle-import:R1206_ENKO")
      (libsource (lib "eagle-import") (part "R-EU_R1206E"))
    )
    (comp (ref "R24")
      (value "1029-3146**RES 1206 7R68 %1")
      (footprint "eagle-import:R1206_ENKO")
      (libsource (lib "eagle-import") (part "R-EU_R1206E"))
    )
    (comp (ref "R25")
      (value "1200970119**RES 1206 100R %5 1/4W")
      (footprint "eagle-import:R1206_ENKO")
      (libsource (lib "eagle-import") (part "R-EU_R1206E"))
    )
    (comp (ref "R26")
      (value "1200970119**RES 1206 100R %5 1/4W")
      (footprint "eagle-import:R1206_ENKO")
      (libsource (lib "eagle-import") (part "R-EU_R1206E"))
    )
    (comp (ref "R27")
      (value "1029-6097**RES 2512 22R %5 1W")
      (footprint "eagle-import:R2512")
      (libsource (lib "eagle-import") (part "R-EU_R2512"))
    )
    (comp (ref "R30")
      (value "1029-6097**RES 2512 22R %5 1W")
      (footprint "eagle-import:R2512")
      (libsource (lib "eagle-import") (part "R-EU_R2512"))
    )
    (comp (ref "R31")
      (value "1029-6097**RES 2512 22R %5 1W")
      (footprint "eagle-import:R2512")
      (libsource (lib "eagle-import") (part "R-EU_R2512"))
    )
    (comp (ref "R33")
      (value "1029-6110**RES 2512 47R %5 1W")
      (footprint "eagle-import:R2512")
      (libsource (lib "eagle-import") (part "R-EU_R2512"))
    )
    (comp (ref "R34")
      (value "1029-6110**RES 2512 47R %5 1W")
      (footprint "eagle-import:R2512")
      (libsource (lib "eagle-import") (part "R-EU_R2512"))
    )
    (comp (ref "R35")
      (value "1029-3008**RES 0805 22R %5")
      (footprint "eagle-import:R0805_ENKO")
      (libsource (lib "eagle-import") (part "R-EU_R0805E"))
    )
    (comp (ref "R36")
      (value "1200970117**RES 1206 0R %5")
      (footprint "eagle-import:R1206_ENKO")
      (libsource (lib "eagle-import") (part "R-EU_R1206E"))
    )
    (comp (ref "R38")
      (value "1200970568**RES 0603 47K %5 1/10W")
      (footprint "eagle-import:R0603_ENKO")
      (libsource (lib "eagle-import") (part "R-EU_R0603E"))
    )
    (comp (ref "R39")
      (value "1200970119**RES 1206 100R %5 1/4W")
      (footprint "eagle-import:R1206_ENKO")
      (libsource (lib "eagle-import") (part "R-EU_R1206E"))
    )
    (comp (ref "R40")
      (value "1200970119**RES 1206 100R %5 1/4W")
      (footprint "eagle-import:R1206_ENKO")
      (libsource (lib "eagle-import") (part "R-EU_R1206E"))
    )
    (comp (ref "R41")
      (value "1200970119**RES 1206 100R %5 1/4W")
      (footprint "eagle-import:R1206_ENKO")
      (libsource (lib "eagle-import") (part "R-EU_R1206E"))
    )
    (comp (ref "R42")
      (value "1200970119**RES 1206 100R %5 1/4W")
      (footprint "eagle-import:R1206_ENKO")
      (libsource (lib "eagle-import") (part "R-EU_R1206E"))
    )
    (comp (ref "R43")
      (value "1200970554**RES 1206 56R %1 1/4W")
      (footprint "eagle-import:R1206_ENKO")
      (libsource (lib "eagle-import") (part "R-EU_R1206E"))
    )
    (comp (ref "R44")
      (value "1200970568**RES 0603 47K %5 1/10W")
      (footprint "eagle-import:R0603_ENKO")
      (libsource (lib "eagle-import") (part "R-EU_R0603E"))
    )
    (comp (ref "R45")
      (value "1319-4060**Ferrite Bead SMD 0805 2kOhm@100MHz 300mA LAIRD HZ0805C202R-10")
      (footprint "eagle-import:R0805_ENKO")
      (libsource (lib "eagle-import") (part "R-EU_R0805E"))
    )
    (comp (ref "R46")
      (value "1200971020**RES 0603 10K %1 1/10W")
      (footprint "eagle-import:R0603_ENKO")
      (libsource (lib "eagle-import") (part "R-EU_R0603E"))
    )
    (comp (ref "R47")
      (value "1200971020**RES 0603 10K %1 1/10W")
      (footprint "eagle-import:R0603_ENKO")
      (libsource (lib "eagle-import") (part "R-EU_R0603E"))
    )
    (comp (ref "R48")
      (value "1200970516**RES 0603 22K %5 1/10W")
      (footprint "eagle-import:R0603_ENKO")
      (libsource (lib "eagle-import") (part "R-EU_R0603E"))
    )
    (comp (ref "R49")
      (value "1029-2005**RES 0603 220R %1")
      (footprint "eagle-import:R0603_ENKO")
      (libsource (lib "eagle-import") (part "R-EU_R0603E"))
    )
    (comp (ref "R50")
      (value "1200970803**RES 0603 100K %1 1/10W")
      (footprint "eagle-import:R0603_ENKO")
      (libsource (lib "eagle-import") (part "R-EU_R0603E"))
    )
    (comp (ref "R51")
      (value "1200971020**RES 0603 10K %1 1/10W")
      (footprint "eagle-import:R0603_ENKO")
      (libsource (lib "eagle-import") (part "R-EU_R0603E"))
    )
    (comp (ref "R52")
      (value "1029-2005**RES 0603 220R %1")
      (footprint "eagle-import:R0603_ENKO")
      (libsource (lib "eagle-import") (part "R-EU_R0603E"))
    )
    (comp (ref "R53")
      (value "1029-2005**RES 0603 220R %1")
      (footprint "eagle-import:R0603_ENKO")
      (libsource (lib "eagle-import") (part "R-EU_R0603E"))
    )
    (comp (ref "R54")
      (value "1200971020**RES 0603 10K %1 1/10W")
      (footprint "eagle-import:R0603_ENKO")
      (libsource (lib "eagle-import") (part "R-EU_R0603E"))
    )
    (comp (ref "R55")
      (value "1029-2233**RES 0603 2K2 %1")
      (footprint "eagle-import:R0603_ENKO")
      (libsource (lib "eagle-import") (part "rcl_334_R-EU_R0603E"))
    )
    (comp (ref "R56")
      (value "1200970522**RES 0603 1K %5 1/10W")
      (footprint "eagle-import:R0603_ENKO")
      (libsource (lib "eagle-import") (part "R-EU_R0603E"))
    )
    (comp (ref "R57")
      (value "1200970803**RES 0603 100K %1 1/10W")
      (footprint "eagle-import:R0603_ENKO")
      (libsource (lib "eagle-import") (part "R-EU_R0603E"))
    )
    (comp (ref "R58")
      (value "1200970770**RES 0603 4K3 %1 1/10W")
      (footprint "eagle-import:R0603_ENKO")
      (libsource (lib "eagle-import") (part "R-EU_R0603E"))
    )
    (comp (ref "R59")
      (value "1200970803**RES 0603 100K %1 1/10W")
      (footprint "eagle-import:R0603_ENKO")
      (libsource (lib "eagle-import") (part "R-EU_R0603E"))
    )
    (comp (ref "R60")
      (value "1029-2234**RES 0603 4K7 %1")
      (footprint "eagle-import:R0603_ENKO")
      (libsource (lib "eagle-import") (part "R-EU_R0603E"))
    )
    (comp (ref "R61")
      (value "1200970583**RES 0603 1K %1 1/10W")
      (footprint "eagle-import:R0603_ENKO")
      (libsource (lib "eagle-import") (part "R-EU_R0603E"))
    )
    (comp (ref "R62")
      (value "1200970706**RES 0603 1K8 %5 1/10W")
      (footprint "eagle-import:R0603_ENKO")
      (libsource (lib "eagle-import") (part "R-EU_R0603E"))
    )
    (comp (ref "R63")
      (value "1029-2003**RES 0603 10R %1")
      (footprint "eagle-import:R0603_ENKO")
      (libsource (lib "eagle-import") (part "R-EU_R0603E"))
    )
    (comp (ref "R64")
      (value "1029-2006**RES 0603 47R %1")
      (footprint "eagle-import:R0603_ENKO")
      (libsource (lib "eagle-import") (part "R-EU_R0603E"))
    )
    (comp (ref "R65")
      (value "1029-6021**RES 2512 0R003 %1 2W")
      (footprint "eagle-import:R2512")
      (libsource (lib "eagle-import") (part "R-EU_R2512"))
    )
    (comp (ref "R66")
      (value "1200970927**RES 0603 100R %1 1/10W")
      (footprint "eagle-import:R0603_ENKO")
      (libsource (lib "eagle-import") (part "R-EU_R0603E"))
    )
    (comp (ref "R67")
      (value "1200970522**RES 0603 1K %5 1/10W")
      (footprint "eagle-import:R0603_ENKO")
      (libsource (lib "eagle-import") (part "R-EU_R0603E"))
    )
    (comp (ref "R68")
      (value "1200970522**RES 0603 1K %5 1/10W")
      (footprint "eagle-import:R0603_ENKO")
      (libsource (lib "eagle-import") (part "R-EU_R0603E"))
    )
    (comp (ref "R69")
      (value "1029-3008**RES 0805 22R %5")
      (footprint "eagle-import:R0805_ENKO")
      (libsource (lib "eagle-import") (part "R-EU_R0805E"))
    )
    (comp (ref "R70")
      (value "1200970843**RES 0603 15K %1 1/10W")
      (footprint "eagle-import:R0603_ENKO")
      (libsource (lib "eagle-import") (part "rcl_334_R-EU_R0603E"))
    )
    (comp (ref "R71")
      (value "1029-2234**RES 0603 4K7 %1")
      (footprint "eagle-import:R0603_ENKO")
      (libsource (lib "eagle-import") (part "R-EU_R0603E"))
    )
    (comp (ref "R72")
      (value "1200970583**RES 0603 1K %1 1/10W")
      (footprint "eagle-import:R0603_ENKO")
      (libsource (lib "eagle-import") (part "R-EU_R0603E"))
    )
    (comp (ref "R73")
      (value "1169-1001**TSM2A103F3951RZ THINKING 0805 10K NTC 125C")
      (footprint "eagle-import:R0805_ENKO")
      (libsource (lib "eagle-import") (part "R-EU_R0805E"))
    )
    (comp (ref "R74")
      (value "1200970194**RES 1206 4K7 %5 1/4W")
      (footprint "eagle-import:R1206_ENKO")
      (libsource (lib "eagle-import") (part "R-EU_R1206E"))
    )
    (comp (ref "R75")
      (value "1200970583**RES 0603 1K %1 1/10W")
      (footprint "eagle-import:R0603_ENKO")
      (libsource (lib "eagle-import") (part "R-EU_R0603E"))
    )
    (comp (ref "R76")
      (value "1200970684**RES 0603 47K %1 1/10W")
      (footprint "eagle-import:R0603_ENKO")
      (libsource (lib "eagle-import") (part "rcl_334_R-EU_R0603E"))
    )
    (comp (ref "R77")
      (value "1029-6089**RES 0603 6K8 %5")
      (footprint "eagle-import:R0603_ENKO")
      (libsource (lib "eagle-import") (part "R-EU_R0603E"))
    )
    (comp (ref "R78")
      (value "1029-2203**RES 0603 12K %1")
      (footprint "eagle-import:R0603_ENKO")
      (libsource (lib "eagle-import") (part "R-EU_R0603E"))
    )
    (comp (ref "R79")
      (value "1029-2341**RES 0603 5K6 %1")
      (footprint "eagle-import:R0603_ENKO")
      (libsource (lib "eagle-import") (part "rcl_334_R-EU_R0603E"))
    )
    (comp (ref "R80")
      (value "1029-2234**RES 0603 4K7 %1")
      (footprint "eagle-import:R0603_ENKO")
      (libsource (lib "eagle-import") (part "rcl_334_R-EU_R0603E"))
    )
    (comp (ref "R81")
      (value "1200970583**RES 0603 1K %1 1/10W")
      (footprint "eagle-import:R0603_ENKO")
      (libsource (lib "eagle-import") (part "R-EU_R0603E"))
    )
    (comp (ref "R82")
      (value "1200971020**RES 0603 10K %1 1/10W")
      (footprint "eagle-import:R0603_ENKO")
      (libsource (lib "eagle-import") (part "R-EU_R0603E"))
    )
    (comp (ref "R83")
      (value "1200970522**RES 0603 1K %5 1/10W")
      (footprint "eagle-import:R0603_ENKO")
      (libsource (lib "eagle-import") (part "R-EU_R0603E"))
    )
    (comp (ref "R84")
      (value "1200970522**RES 0603 1K %5 1/10W")
      (footprint "eagle-import:R0603_ENKO")
      (libsource (lib "eagle-import") (part "R-EU_R0603E"))
    )
    (comp (ref "R85")
      (value "1169-1006**FUSE SMD 1206 PTC RESETTABLE 16V IHOLD=0.75A IMAX=100A")
      (footprint "eagle-import:R1206_ENKO")
      (libsource (lib "eagle-import") (part "R-EU_R1206E"))
    )
    (comp (ref "R86")
      (value "1200970522**RES 0603 1K %5 1/10W")
      (footprint "eagle-import:R0603_ENKO")
      (libsource (lib "eagle-import") (part "R-EU_R0603E"))
    )
    (comp (ref "R87")
      (value "1200971020**RES 0603 10K %1 1/10W")
      (footprint "eagle-import:R0603_ENKO")
      (libsource (lib "eagle-import") (part "R-EU_R0603E"))
    )
    (comp (ref "R88")
      (value "1029-2234**RES 0603 4K7 %1")
      (footprint "eagle-import:R0603_ENKO")
      (libsource (lib "eagle-import") (part "R-EU_R0603E"))
    )
    (comp (ref "R89")
      (value "1200970583**RES 0603 1K %1 1/10W")
      (footprint "eagle-import:R0603_ENKO")
      (libsource (lib "eagle-import") (part "R-EU_R0603E"))
    )
    (comp (ref "R90")
      (value "1029-2231**RES 0603 1K8 %1")
      (footprint "eagle-import:R0603_ENKO")
      (libsource (lib "eagle-import") (part "R-EU_R0603E"))
    )
    (comp (ref "R91")
      (value "1200971020**RES 0603 10K %1 1/10W")
      (footprint "eagle-import:R0603_ENKO")
      (libsource (lib "eagle-import") (part "R-EU_R0603E"))
    )
    (comp (ref "R92")
      (value "1200970568**RES 0603 47K %5 1/10W")
      (footprint "eagle-import:R0603_ENKO")
      (libsource (lib "eagle-import") (part "R-EU_R0603E"))
    )
    (comp (ref "R93")
      (value "1409-0025**RES 0603 470R %5 1/16W")
      (footprint "eagle-import:R0603_ENKO")
      (libsource (lib "eagle-import") (part "R-EU_R0603E"))
    )
    (comp (ref "R94")
      (value "1029-6086**RES 0603 22R %1")
      (footprint "eagle-import:R0603_ENKO")
      (libsource (lib "eagle-import") (part "R-EU_R0603E"))
    )
    (comp (ref "R95")
      (value "NC**TAKILMAYACAK")
      (footprint "eagle-import:R0603_ENKO")
      (libsource (lib "eagle-import") (part "R-EU_R0603E"))
    )
    (comp (ref "R96")
      (value "1029-6086**RES 0603 22R %1")
      (footprint "eagle-import:R0603_ENKO")
      (libsource (lib "eagle-import") (part "R-EU_R0603E"))
    )
    (comp (ref "R97")
      (value "1029-6086**RES 0603 22R %1")
      (footprint "eagle-import:R0603_ENKO")
      (libsource (lib "eagle-import") (part "R-EU_R0603E"))
    )
    (comp (ref "R98")
      (value "1029-2234**RES 0603 4K7 %1")
      (footprint "eagle-import:R0603_ENKO")
      (libsource (lib "eagle-import") (part "R-EU_R0603E"))
    )
    (comp (ref "R99")
      (value "NC**TAKILMAYACAK")
      (footprint "eagle-import:R0603_ENKO")
      (libsource (lib "eagle-import") (part "R-EU_R0603E"))
    )
    (comp (ref "R100")
      (value "1200970852**RES 0603 1K5 %5 1/10W ( <-1029-3501 )")
      (footprint "eagle-import:R0603_ENKO")
      (libsource (lib "eagle-import") (part "R-EU_R0603E"))
    )
    (comp (ref "R101")
      (value "1200970684**RES 0603 47K %1 1/10W")
      (footprint "eagle-import:R0603_ENKO")
      (libsource (lib "eagle-import") (part "R-EU_R0603E"))
    )
    (comp (ref "R102")
      (value "1200970583**RES 0603 1K %1 1/10W")
      (footprint "eagle-import:R0603_ENKO")
      (libsource (lib "eagle-import") (part "R-EU_R0603E"))
    )
    (comp (ref "R103")
      (value "1200970522**RES 0603 1K %5 1/10W")
      (footprint "eagle-import:R0603_ENKO")
      (libsource (lib "eagle-import") (part "R-EU_R0603E"))
    )
    (comp (ref "R104")
      (value "1200970522**RES 0603 1K %5 1/10W")
      (footprint "eagle-import:R0603_ENKO")
      (libsource (lib "eagle-import") (part "R-EU_R0603E"))
    )
    (comp (ref "R105")
      (value "1029-2229**RES 0603 120K %1")
      (footprint "eagle-import:R0603_ENKO")
      (libsource (lib "eagle-import") (part "R-EU_R0603E"))
    )
    (comp (ref "R106")
      (value "1029-2219**RES 0603 30K %1")
      (footprint "eagle-import:R0603_ENKO")
      (libsource (lib "eagle-import") (part "R-EU_R0603E"))
    )
    (comp (ref "R107")
      (value "1200970515**RES 0603 100K %5 1/10W")
      (footprint "eagle-import:R0603_ENKO")
      (libsource (lib "eagle-import") (part "R-EU_R0603E"))
    )
    (comp (ref "R108")
      (value "1200970730**RES 0603 560R %1 1/10W")
      (footprint "eagle-import:R0603_ENKO")
      (libsource (lib "eagle-import") (part "R-EU_R0603E"))
    )
    (comp (ref "R109")
      (value "1200971020**RES 0603 10K %1 1/10W")
      (footprint "eagle-import:R0603_ENKO")
      (libsource (lib "eagle-import") (part "R-EU_R0603E"))
    )
    (comp (ref "R110")
      (value "1200970516**RES 0603 22K %5 1/10W")
      (footprint "eagle-import:R0603_ENKO")
      (libsource (lib "eagle-import") (part "R-EU_R0603E"))
    )
    (comp (ref "R112")
      (value "1200970156**RES 1206 22K %5 1/4W")
      (footprint "eagle-import:R1206_ENKO")
      (libsource (lib "eagle-import") (part "R-EU_R1206E"))
    )
    (comp (ref "R113")
      (value "1200970121**RES 0805 1K %5 1/8W")
      (footprint "eagle-import:R0805_ENKO")
      (libsource (lib "eagle-import") (part "R-EU_R0805E"))
    )
    (comp (ref "R114")
      (value "1200971020**RES 0603 10K %1 1/10W")
      (footprint "eagle-import:R0603_ENKO")
      (libsource (lib "eagle-import") (part "R-EU_R0603E"))
    )
    (comp (ref "R115")
      (value "1200970156**RES 1206 22K %5 1/4W")
      (footprint "eagle-import:R1206_ENKO")
      (libsource (lib "eagle-import") (part "R-EU_R1206E"))
    )
    (comp (ref "R116")
      (value "1200970585**RES 0603 1M %5 1/10W")
      (footprint "eagle-import:R0603_ENKO")
      (libsource (lib "eagle-import") (part "R-EU_R0603E"))
    )
    (comp (ref "R117")
      (value "1029-6015**RES 1206 56K %5")
      (footprint "eagle-import:R1206_ENKO")
      (libsource (lib "eagle-import") (part "R-EU_R1206E"))
    )
    (comp (ref "R118")
      (value "1029-6105**RES 2512 330mR %1 2W")
      (footprint "eagle-import:R2512")
      (libsource (lib "eagle-import") (part "R-EU_R2512"))
    )
    (comp (ref "R119")
      (value "1029-6105**RES 2512 330mR %1 2W")
      (footprint "eagle-import:R2512")
      (libsource (lib "eagle-import") (part "R-EU_R2512"))
    )
    (comp (ref "R133")
      (value "1200970626**RES 0603 82K %1 1/10W")
      (footprint "eagle-import:R0603_ENKO")
      (libsource (lib "eagle-import") (part "R-EU_R0603E"))
    )
    (comp (ref "R134")
      (value "1029-2234**RES 0603 4K7 %1")
      (footprint "eagle-import:R0603_ENKO")
      (libsource (lib "eagle-import") (part "R-EU_R0603E"))
    )
    (comp (ref "R135")
      (value "1200970940**RES 0603 6K8 %1 1/10W")
      (footprint "eagle-import:R0603_ENKO")
      (libsource (lib "eagle-import") (part "R-EU_R0603E"))
    )
    (comp (ref "R193")
      (value "1200970934**RES 0603 470K %1 1/10W")
      (footprint "eagle-import:R0603_ENKO")
      (libsource (lib "eagle-import") (part "R-EU_R0603E"))
    )
    (comp (ref "R194")
      (value "1200970528**RES 0603 0R %5 1/10W")
      (footprint "eagle-import:R0603_ENKO")
      (libsource (lib "eagle-import") (part "R-EU_R0603E"))
    )
    (comp (ref "RL1")
      (value "1200930051**RELAY SPST 12V 5A 7x15x20.3mm")
      (footprint "eagle-import:ALD1_AND_ALJ_RELAY")
      (libsource (lib "eagle-import") (part "ALD1_AND_ALJ_RELAY"))
    )
    (comp (ref "STENCIL")
      (value "041-7554**SDA381V7 için Çerçeveli Elek (Stencil) (600x600)")
      (footprint "eagle-import:PCB")
      (libsource (lib "eagle-import") (part "PCB"))
    )
    (comp (ref "T1")
      (value "1109-1016**Transistor NPN 3A 100V 15W Hfemin:10 DPAK Diodes MJD31C-13")
      (footprint "eagle-import:DPAK")
      (libsource (lib "eagle-import") (part "MJD31C"))
    )
    (comp (ref "T1_X")
      (value "NC**TAKILMAYACAK (Not Fitted)")
      (footprint "eagle-import:SOT23")
      (libsource (lib "eagle-import") (part "BC848SMDALT1"))
    )
    (comp (ref "T3")
      (value "1200980091**TRANS SMD PNP BC857B SOT-23")
      (footprint "eagle-import:SOT23-BEC")
      (libsource (lib "eagle-import") (part "-PNP-SOT23-BECBC856B"))
    )
    (comp (ref "T4")
      (value "1200980090**TRANS SMD NPN BC847B SOT-23")
      (footprint "eagle-import:SOT23")
      (libsource (lib "eagle-import") (part "BC848SMDALT1"))
    )
    (comp (ref "T5")
      (value "1200980090**TRANS SMD NPN BC847B SOT-23")
      (footprint "eagle-import:SOT23")
      (libsource (lib "eagle-import") (part "BC848SMDALT1"))
    )
    (comp (ref "T6")
      (value "NC**TAKILMAYACAK")
      (footprint "eagle-import:SOT23")
      (libsource (lib "eagle-import") (part "BC848SMDALT1"))
    )
    (comp (ref "T7")
      (value "1200980090**TRANS SMD NPN BC847B SOT-23")
      (footprint "eagle-import:SOT23")
      (libsource (lib "eagle-import") (part "BC848SMDALT1"))
    )
    (comp (ref "T9")
      (value "1200980090**TRANS SMD NPN BC847B SOT-23")
      (footprint "eagle-import:SOT23")
      (libsource (lib "eagle-import") (part "BC848SMDALT1"))
    )
    (comp (ref "T10")
      (value "1049-1012**MMBTA56 PNP 80V 500mA 330mW hfe(min):100 SOT23")
      (footprint "eagle-import:SOT23-BEC")
      (libsource (lib "eagle-import") (part "-PNP-SOT23-BECBC856B"))
    )
    (comp (ref "TP1")
      (value "PTR1TP20R")
      (footprint "eagle-import:TP20R")
      (libsource (lib "eagle-import") (part "PTR1TP20R"))
    )
    (comp (ref "TP4")
      (value "PTR1TP20R")
      (footprint "eagle-import:TP20R")
      (libsource (lib "eagle-import") (part "PTR1TP20R"))
    )
    (comp (ref "TRF1")
      (value "0319-7458**SMPS TRAFO 90W E36/18/11 2*60uH (Insulation Improved 0319-7451) DBC2")
      (footprint "eagle-import:DEIF_TRF")
      (libsource (lib "eagle-import") (part "DEIF_TRF"))
    )
    (comp (ref "TVS1")
      (value "1119-3061**5V 130W TVS Diode SOD-323")
      (footprint "eagle-import:SOD323")
      (libsource (lib "eagle-import") (part "TVS-BD-SOD323"))
    )
    (comp (ref "U1")
      (value "1039-2220**STM32F072C8T6 64K Flash USB, CAN")
      (footprint "eagle-import:STM32F072CXXX_LQFP48")
      (libsource (lib "eagle-import") (part "STM32F072CXXX_LQFP48"))
    )
    (comp (ref "U2")
      (value "1039-2392**LMR16006XDDCR 0.6A, 0.7MHz Step-Down Converter in a TSOT-6L, Input 4V to 60V")
      (footprint "eagle-import:AOZ1282CI-1")
      (libsource (lib "eagle-import") (part "AOZ1282CI-1"))
    )
    (comp (ref "X1")
      (value "0289-1472**WR-TBL Series 3134 - 3 kutup 7.62 mm Close Hor. PCB Header (Wurth 691 313 410 003)")
      (footprint "eagle-import:GMSTBA3")
      (fields (field (name "MF") "FARNELL") (field (name "MPN") "1757255"))
      (libsource (lib "eagle-import") (part "GMSTBA3"))
    )
    (comp (ref "X1-K")
      (value "0289-1473**WR-TBL Series 3524 - 3 kutup 7.62 mm Hor. w. Hook on Wire Side (Wurth 691 352 410 003)")
      (footprint "eagle-import:SOKET")
      (libsource (lib "eagle-import") (part "SOKET"))
    )
    (comp (ref "X2")
      (value "0309-1064**USB Type-B Mini Connector Horizantal")
      (footprint "eagle-import:USB_B(YATIK)")
      (libsource (lib "eagle-import") (part "USB_B(YATIK)"))
    )
    (comp (ref "X3")
      (value "0289-1470**WR-TBL Series 313 - 4 kutup 5.08 mm Close Hor. PCB Header (Wurth 691 313 510 004)")
      (footprint "eagle-import:MSTBA4")
      (fields (field (name "MF") "FARNELL") (field (name "MPN") "1757268"))
      (libsource (lib "eagle-import") (part "MSTBA4"))
    )
    (comp (ref "X3-K")
      (value "0289-1471**WR-TBL Series 352 - 4 kutup 5.08 mm Hor. with Hook on Wire Side (wurth 691 352 510 004)")
      (footprint "eagle-import:SOKET")
      (libsource (lib "eagle-import") (part "SOKET"))
    )
    (comp (ref "X4")
      (value "0289-1474**WR-TBL Series 313 - 3 kutup 5.08 mm Close Hor. PCB Header (Wurth 691 313 510 003)")
      (footprint "eagle-import:MSTBA3")
      (fields (field (name "MF") "FARNELL") (field (name "MPN") "1757255"))
      (libsource (lib "eagle-import") (part "MSTBA3"))
    )
    (comp (ref "X4-K")
      (value "0289-1475**WR-TBL Series 352 - 3 kutup 5.08 mm Hor. with Hook on Wire Side (wurth 691 352 510 003)")
      (footprint "eagle-import:SOKET")
      (libsource (lib "eagle-import") (part "SOKET"))
    )
    (comp (ref "Z1")
      (value "1129-1195**ZENER SOT23 18V 400mW %5 BZX84C18V")
      (footprint "eagle-import:SOT23")
      (libsource (lib "eagle-import") (part "ZENER-DIODESOT23"))
    )
    (comp (ref "Z2")
      (value "NC**TAKILMAYACAK (Not Fitted)")
      (footprint "eagle-import:SOT23")
      (libsource (lib "eagle-import") (part "ZENER-DIODESOT23"))
    )
    (comp (ref "Z4")
      (value "1129-1162**ZENER SOT23 3V9 300mW BZX84C3V9")
      (footprint "eagle-import:SOT23")
      (libsource (lib "eagle-import") (part "ZENER-DIODESOT23"))
    )
    (comp (ref "Z5")
      (value "1129-1151**ZENER SOT23 12V 225mW BZX84C12")
      (footprint "eagle-import:SOT23")
      (libsource (lib "eagle-import") (part "ZENER-DIODESOT23"))
    )
    (comp (ref "Z6")
      (value "1129-1146**ZENER SOT23 2V7 300mW BZX84C2V7")
      (footprint "eagle-import:SOT23")
      (libsource (lib "eagle-import") (part "ZENER-DIODESOT23"))
    )
    (comp (ref "Z7")
      (value "1129-1151**ZENER SOT23 12V 225mW BZX84C12")
      (footprint "eagle-import:SOT23")
      (libsource (lib "eagle-import") (part "ZENER-DIODESOT23"))
    )
    (comp (ref "Z8")
      (value "1129-1140**ZENER SOT23 5V1 0.4W BZX84C5V1")
      (footprint "eagle-import:SOT23")
      (libsource (lib "eagle-import") (part "ZENER-DIODESOT23"))
    )
  )
  (nets
    (net (code "1") (name "+3V3") (class "Default")
      (node (ref "C38") (pin "1") (pinfunction "1_1") (pintype "passive"))
      (node (ref "C39") (pin "1") (pinfunction "1_1") (pintype "passive"))
      (node (ref "C45") (pin "1") (pinfunction "1_1") (pintype "passive"))
      (node (ref "C48") (pin "1") (pinfunction "1_1") (pintype "passive"))
      (node (ref "C49") (pin "1") (pinfunction "1_1") (pintype "passive"))
      (node (ref "C51") (pin "1") (pinfunction "1_1") (pintype "passive"))
      (node (ref "C54") (pin "1") (pinfunction "1_1") (pintype "passive"))
      (node (ref "C55") (pin "1") (pinfunction "1_1") (pintype "passive"))
      (node (ref "C57") (pin "1") (pinfunction "1_1") (pintype "passive"))
      (node (ref "D13") (pin "2") (pinfunction "C_2") (pintype "passive"))
      (node (ref "IC4") (pin "3") (pinfunction "OUT_3") (pintype "passive"))
      (node (ref "IC5") (pin "8") (pinfunction "V+_8") (pintype "power_in"))
      (node (ref "LED1") (pin "2") (pinfunction "2_2") (pintype "passive"))
      (node (ref "PROG1") (pin "1") (pinfunction "+3V3_1") (pintype "passive"))
      (node (ref "PROG2") (pin "1") (pinfunction "+3V3_1") (pintype "passive"))
      (node (ref "R100") (pin "2") (pinfunction "2_2") (pintype "passive"))
      (node (ref "R110") (pin "2") (pinfunction "2_2") (pintype "passive"))
      (node (ref "R45") (pin "2") (pinfunction "2_2") (pintype "passive"))
      (node (ref "R46") (pin "1") (pinfunction "1_1") (pintype "passive"))
      (node (ref "R72") (pin "2") (pinfunction "2_2") (pintype "passive"))
      (node (ref "U1") (pin "24") (pinfunction "VDD._24") (pintype "bidirectional"))
      (node (ref "U1") (pin "36") (pinfunction "VDDIO2_36") (pintype "bidirectional"))
      (node (ref "U1") (pin "48") (pinfunction "VDD_48") (pintype "bidirectional"))
    )
    (net (code "2") (name "/13.8V+") (class "Default")
      (node (ref "C18") (pin "P$1") (pinfunction "1_P$1") (pintype "passive"))
      (node (ref "C24") (pin "P$1") (pinfunction "1_P$1") (pintype "passive"))
      (node (ref "C36") (pin "1") (pinfunction "1_1") (pintype "passive"))
      (node (ref "C37") (pin "1") (pinfunction "1_1") (pintype "passive"))
      (node (ref "C40") (pin "+") (pinfunction "+_+") (pintype "passive"))
      (node (ref "C40") (pin "+1") (pinfunction "+_+1") (pintype "passive"))
      (node (ref "C42") (pin "+") (pinfunction "+_+") (pintype "passive"))
      (node (ref "C72") (pin "2") (pinfunction "2_2") (pintype "passive"))
      (node (ref "C73") (pin "1") (pinfunction "1_1") (pintype "passive"))
      (node (ref "C74") (pin "P$1") (pinfunction "1_P$1") (pintype "passive"))
      (node (ref "C86") (pin "1") (pinfunction "1_1") (pintype "passive"))
      (node (ref "C88") (pin "P$1") (pinfunction "1_P$1") (pintype "passive"))
      (node (ref "D7") (pin "A") (pinfunction "A_A") (pintype "passive"))
      (node (ref "L4") (pin "1") (pinfunction "1_1") (pintype "passive"))
      (node (ref "OC2") (pin "1") (pinfunction "1_1") (pintype "passive"))
      (node (ref "R117") (pin "1") (pinfunction "1_1") (pintype "passive"))
      (node (ref "R50") (pin "1") (pinfunction "1_1") (pintype "passive"))
      (node (ref "R78") (pin "2") (pinfunction "2_2") (pintype "passive"))
      (node (ref "TRF1") (pin "10") (pinfunction "13_10") (pintype "passive"))
      (node (ref "TRF1") (pin "21") (pinfunction "13_21") (pintype "passive"))
      (node (ref "TRF1") (pin "22") (pinfunction "12_22") (pintype "passive"))
      (node (ref "TRF1") (pin "29") (pinfunction "12_29") (pintype "passive"))
      (node (ref "TRF1") (pin "30") (pinfunction "13_30") (pintype "passive"))
      (node (ref "TRF1") (pin "43") (pinfunction "12_43") (pintype "passive"))
      (node (ref "TRF1") (pin "44") (pinfunction "13_44") (pintype "passive"))
      (node (ref "TRF1") (pin "9") (pinfunction "12_9") (pintype "passive"))
    )
    (net (code "3") (name "/I_FOR_REV_BAT_PROTEC") (class "Default")
      (node (ref "C50") (pin "2") (pinfunction "2_2") (pintype "passive"))
      (node (ref "IC5") (pin "3") (pinfunction "+IN_3") (pintype "input"))
      (node (ref "IC5") (pin "7") (pinfunction "OUT_7") (pintype "output"))
      (node (ref "R109") (pin "2") (pinfunction "2_2") (pintype "passive"))
      (node (ref "R71") (pin "2") (pinfunction "2_2") (pintype "passive"))
    )
    (net (code "4") (name "/N$31") (class "Default")
      (node (ref "C84") (pin "-") (pinfunction "-_-") (pintype "passive"))
      (node (ref "C84_X") (pin "-") (pinfunction "-_-") (pintype "passive"))
      (node (ref "C85") (pin "2") (pinfunction "2_2") (pintype "passive"))
      (node (ref "IC8") (pin "S") (pinfunction "S123_S") (pintype "passive"))
      (node (ref "IC8") (pin "S1") (pinfunction "S123_S1") (pintype "passive"))
      (node (ref "IC8") (pin "S2") (pinfunction "S123_S2") (pintype "passive"))
      (node (ref "L4") (pin "3") (pinfunction "3_3") (pintype "passive"))
    )
    (net (code "5") (name "/N$69") (class "Default")
      (node (ref "C46") (pin "1") (pinfunction "1_1") (pintype "passive"))
      (node (ref "C71") (pin "2") (pinfunction "2_2") (pintype "passive"))
      (node (ref "C86") (pin "2") (pinfunction "2_2") (pintype "passive"))
      (node (ref "IC3") (pin "6") (pinfunction "GND_6") (pintype "power_in"))
      (node (ref "L4") (pin "2") (pinfunction "2_2") (pintype "passive"))
      (node (ref "R114") (pin "2") (pinfunction "2_2") (pintype "passive"))
      (node (ref "R116") (pin "1") (pinfunction "1_1") (pintype "passive"))
      (node (ref "R65") (pin "2") (pinfunction "2_2") (pintype "passive"))
      (node (ref "R66") (pin "2") (pinfunction "2_2") (pintype "passive"))
      (node (ref "R67") (pin "2") (pinfunction "2_2") (pintype "passive"))
      (node (ref "R80") (pin "1") (pinfunction "1_1") (pintype "passive"))
      (node (ref "T7") (pin "2") (pinfunction "E_2") (pintype "passive"))
      (node (ref "T9") (pin "2") (pinfunction "E_2") (pintype "passive"))
      (node (ref "Z7") (pin "1") (pinfunction "A_1") (pintype "passive"))
      (node (ref "Z8") (pin "1") (pinfunction "A_1") (pintype "passive"))
    )
    (net (code "6") (name "/N$84") (class "Default")
      (node (ref "C21") (pin "1") (pinfunction "1_1") (pintype "passive"))
      (node (ref "IC2") (pin "6") (pinfunction "6.CS_6") (pintype "input"))
      (node (ref "Q2") (pin "D") (pinfunction "D_D") (pintype "passive"))
      (node (ref "TRF1") (pin "11") (pinfunction "14_11") (pintype "passive"))
      (node (ref "TRF1") (pin "12") (pinfunction "15_12") (pintype "passive"))
      (node (ref "TRF1") (pin "13") (pinfunction "16_13") (pintype "passive"))
      (node (ref "TRF1") (pin "19") (pinfunction "15_19") (pintype "passive"))
      (node (ref "TRF1") (pin "20") (pinfunction "14_20") (pintype "passive"))
      (node (ref "TRF1") (pin "25") (pinfunction "16_25") (pintype "passive"))
      (node (ref "TRF1") (pin "31") (pinfunction "14_31") (pintype "passive"))
      (node (ref "TRF1") (pin "32") (pinfunction "15_32") (pintype "passive"))
      (node (ref "TRF1") (pin "38") (pinfunction "16_38") (pintype "passive"))
      (node (ref "TRF1") (pin "45") (pinfunction "14_45") (pintype "passive"))
      (node (ref "TRF1") (pin "46") (pinfunction "15_46") (pintype "passive"))
      (node (ref "TRF1") (pin "47") (pinfunction "16_47") (pintype "passive"))
    )
    (net (code "7") (name "/OSC1") (class "Default")
      (node (ref "C23") (pin "1") (pinfunction "1_1") (pintype "passive"))
      (node (ref "Q3") (pin "1") (pinfunction "1_1") (pintype "passive"))
      (node (ref "U1") (pin "5") (pinfunction "PF0/OSC_IN_5") (pintype "bidirectional"))
    )
    (net (code "8") (name "/OSC2") (class "Default")
      (node (ref "C26") (pin "1") (pinfunction "1_1") (pintype "passive"))
      (node (ref "Q3") (pin "2") (pinfunction "2_2") (pintype "passive"))
      (node (ref "U1") (pin "6") (pinfunction "PF1/OSC_OUT_6") (pintype "bidirectional"))
    )
    (net (code "9") (name "/PRI_SOURCE") (class "Default")
      (node (ref "C22") (pin "P$2") (pinfunction "2_P$2") (pintype "passive"))
      (node (ref "C25") (pin "2") (pinfunction "2_2") (pintype "passive"))
      (node (ref "H1") (pin "1") (pinfunction "P$1_1") (pintype "bidirectional"))
      (node (ref "H1") (pin "2") (pinfunction "P$1_2") (pintype "bidirectional"))
      (node (ref "H1") (pin "3") (pinfunction "P$2_3") (pintype "bidirectional"))
      (node (ref "H1") (pin "4") (pinfunction "P$2_4") (pintype "bidirectional"))
      (node (ref "Q1") (pin "S") (pinfunction "S_S") (pintype "passive"))
      (node (ref "R118") (pin "2") (pinfunction "2_2") (pintype "passive"))
      (node (ref "R119") (pin "2") (pinfunction "2_2") (pintype "passive"))
      (node (ref "R21") (pin "1") (pinfunction "1_1") (pintype "passive"))
      (node (ref "R27") (pin "1") (pinfunction "1_1") (pintype "passive"))
      (node (ref "R6") (pin "2") (pinfunction "2_2") (pintype "passive"))
    )
    (net (code "10") (name "/REG_INP") (class "Default")
      (node (ref "C47") (pin "1") (pinfunction "1_1") (pintype "passive"))
      (node (ref "D8") (pin "C") (pinfunction "C_C") (pintype "passive"))
      (node (ref "D9") (pin "3") (pinfunction "C_3") (pintype "passive"))
      (node (ref "IC4") (pin "2") (pinfunction "IN_2") (pintype "input"))
      (node (ref "IC4") (pin "4") (pinfunction "IN_4") (pintype "input"))
    )
    (net (code "11") (name "/RES") (class "Default")
      (node (ref "C28") (pin "2") (pinfunction "2_2") (pintype "passive"))
      (node (ref "IC2") (pin "4") (pinfunction "4.LLD_4") (pintype "input"))
      (node (ref "R44") (pin "1") (pinfunction "1_1") (pintype "passive"))
    )
    (net (code "12") (name "/VAUX_DC") (class "Default")
      (node (ref "C110") (pin "2") (pinfunction "2_2") (pintype "passive"))
      (node (ref "C20") (pin "+") (pinfunction "+_+") (pintype "passive"))
      (node (ref "D6") (pin "C") (pinfunction "C_C") (pintype "passive"))
      (node (ref "D7") (pin "C") (pinfunction "C_C") (pintype "passive"))
      (node (ref "R193") (pin "2") (pinfunction "2_2") (pintype "passive"))
      (node (ref "R35") (pin "2") (pinfunction "2_2") (pintype "passive"))
      (node (ref "U2") (pin "5") (pinfunction "VIN_5") (pintype "bidirectional"))
    )
    (net (code "13") (name "/VDC_BUS") (class "Default")
      (node (ref "B1") (pin "+") (pinfunction "+_+") (pintype "passive"))
      (node (ref "C11") (pin "2") (pinfunction "2_2") (pintype "passive"))
      (node (ref "C12") (pin "+") (pinfunction "+_+") (pintype "passive"))
      (node (ref "C24") (pin "P$2") (pinfunction "2_P$2") (pintype "passive"))
      (node (ref "C27") (pin "2") (pinfunction "2_2") (pintype "passive"))
      (node (ref "C76") (pin "1") (pinfunction "1_1") (pintype "passive"))
      (node (ref "C82") (pin "1") (pinfunction "1_1") (pintype "passive"))
      (node (ref "D2") (pin "A") (pinfunction "A_A") (pintype "passive"))
      (node (ref "D3") (pin "A") (pinfunction "A_A") (pintype "passive"))
      (node (ref "R11") (pin "2") (pinfunction "2_2") (pintype "passive"))
      (node (ref "R9") (pin "2") (pinfunction "2_2") (pintype "passive"))
      (node (ref "TRF1") (pin "16") (pinfunction "4_16") (pintype "passive"))
      (node (ref "TRF1") (pin "3") (pinfunction "4_3") (pintype "passive"))
      (node (ref "TRF1") (pin "35") (pinfunction "4_35") (pintype "passive"))
      (node (ref "TRF1") (pin "52") (pinfunction "4_52") (pintype "passive"))
    )
    (net (code "14") (name "/VREF2.1") (class "Default")
      (node (ref "IC3") (pin "1") (pinfunction "VREF_1") (pintype "bidirectional"))
      (node (ref "IC3") (pin "5") (pinfunction "CV+_5") (pintype "input"))
      (node (ref "R61") (pin "2") (pinfunction "2_2") (pintype "passive"))
    )
    (net (code "15") (name "/V_FB2") (class "Default")
      (node (ref "C78") (pin "1") (pinfunction "1_1") (pintype "passive"))
      (node (ref "R134") (pin "1") (pinfunction "1_1") (pintype "passive"))
      (node (ref "R135") (pin "2") (pinfunction "2_2") (pintype "passive"))
      (node (ref "U2") (pin "3") (pinfunction "FB_3") (pintype "bidirectional"))
    )
    (net (code "16") (name "/V_SUPPLY") (class "Default")
      (node (ref "C33") (pin "2") (pinfunction "2_2") (pintype "passive"))
      (node (ref "C34") (pin "2") (pinfunction "2_2") (pintype "passive"))
      (node (ref "C61") (pin "1") (pinfunction "1_1") (pintype "passive"))
      (node (ref "C69") (pin "2") (pinfunction "2_2") (pintype "passive"))
      (node (ref "C79") (pin "2") (pinfunction "2_2") (pintype "passive"))
      (node (ref "C98") (pin "2") (pinfunction "2_2") (pintype "passive"))
      (node (ref "D10") (pin "C") (pinfunction "C_C") (pintype "passive"))
      (node (ref "D8") (pin "A") (pinfunction "A_A") (pintype "passive"))
      (node (ref "IC2") (pin "1") (pinfunction "1.VCC_1") (pintype "power_in"))
      (node (ref "IC9") (pin "8") (pinfunction "V+_8") (pintype "power_in"))
      (node (ref "L5") (pin "1") (pinfunction "2_1") (pintype "passive"))
      (node (ref "OC1") (pin "1") (pinfunction "1_1") (pintype "passive"))
      (node (ref "R107") (pin "2") (pinfunction "2_2") (pintype "passive"))
      (node (ref "R133") (pin "2") (pinfunction "2_2") (pintype "passive"))
      (node (ref "R69") (pin "1") (pinfunction "1_1") (pintype "passive"))
      (node (ref "R88") (pin "2") (pinfunction "2_2") (pintype "passive"))
      (node (ref "R92") (pin "1") (pinfunction "1_1") (pintype "passive"))
      (node (ref "RL1") (pin "2") (pinfunction "2_2") (pintype "passive"))
    )
    (net (code "17") (name "BOOST_INP") (class "Default")
      (node (ref "C63") (pin "1") (pinfunction "1_1") (pintype "passive"))
      (node (ref "R91") (pin "1") (pinfunction "1_1") (pintype "passive"))
      (node (ref "TP1") (pin "TP") (pinfunction "TP_TP") (pintype "input"))
      (node (ref "U1") (pin "15") (pinfunction "PA5_15") (pintype "bidirectional"))
    )
    (net (code "18") (name "CUT_OFF_OUTPUT") (class "Default")
      (node (ref "C71") (pin "1") (pinfunction "1_1") (pintype "passive"))
      (node (ref "D14") (pin "A") (pinfunction "A_A") (pintype "passive"))
      (node (ref "R110") (pin "1") (pinfunction "1_1") (pintype "passive"))
      (node (ref "U1") (pin "16") (pinfunction "PA6_16") (pintype "bidirectional"))
    )
    (net (code "19") (name "EARTH") (class "Default")
      (node (ref "C11") (pin "1") (pinfunction "1_1") (pintype "passive"))
      (node (ref "C25") (pin "1") (pinfunction "1_1") (pintype "passive"))
      (node (ref "C27") (pin "1") (pinfunction "1_1") (pintype "passive"))
      (node (ref "C35") (pin "2") (pinfunction "2_2") (pintype "passive"))
      (node (ref "C4") (pin "1") (pinfunction "1_1") (pintype "passive"))
      (node (ref "C5") (pin "2") (pinfunction "2_2") (pintype "passive"))
      (node (ref "C59") (pin "1") (pinfunction "1_1") (pintype "passive"))
      (node (ref "C7") (pin "1") (pinfunction "1_1") (pintype "passive"))
      (node (ref "C73") (pin "2") (pinfunction "2_2") (pintype "passive"))
      (node (ref "C74") (pin "P$2") (pinfunction "2_P$2") (pintype "passive"))
      (node (ref "C75") (pin "P$2") (pinfunction "2_P$2") (pintype "passive"))
      (node (ref "C87") (pin "P$2") (pinfunction "2_P$2") (pintype "passive"))
      (node (ref "C88") (pin "P$2") (pinfunction "2_P$2") (pintype "passive"))
      (node (ref "C89") (pin "1") (pinfunction "1_1") (pintype "passive"))
      (node (ref "C89") (pin "3") (pinfunction "1_3") (pintype "passive"))
      (node (ref "C90") (pin "2") (pinfunction "2_2") (pintype "passive"))
      (node (ref "C90") (pin "4") (pinfunction "2_4") (pintype "passive"))
      (node (ref "X1") (pin "3") (pinfunction "1_3") (pintype "passive"))
    )
    (net (code "20") (name "GND") (class "Default")
      (node (ref "B1") (pin "-") (pinfunction "-_-") (pintype "passive"))
      (node (ref "C10") (pin "-") (pinfunction "-_-") (pintype "passive"))
      (node (ref "C12") (pin "-") (pinfunction "-_-") (pintype "passive"))
      (node (ref "C13") (pin "-") (pinfunction "-_-") (pintype "passive"))
      (node (ref "C14") (pin "2") (pinfunction "2_2") (pintype "passive"))
      (node (ref "C15") (pin "2") (pinfunction "2_2") (pintype "passive"))
      (node (ref "C18") (pin "P$2") (pinfunction "2_P$2") (pintype "passive"))
      (node (ref "C29") (pin "1") (pinfunction "1_1") (pintype "passive"))
      (node (ref "C59") (pin "2") (pinfunction "2_2") (pintype "passive"))
      (node (ref "C6") (pin "2") (pinfunction "2_2") (pintype "passive"))
      (node (ref "C7") (pin "2") (pinfunction "2_2") (pintype "passive"))
      (node (ref "C76") (pin "2") (pinfunction "2_2") (pintype "passive"))
      (node (ref "C8") (pin "2") (pinfunction "2_2") (pintype "passive"))
      (node (ref "C82") (pin "2") (pinfunction "2_2") (pintype "passive"))
      (node (ref "C9") (pin "1") (pinfunction "1_1") (pintype "passive"))
      (node (ref "IC1") (pin "4") (pinfunction "GND_4") (pintype "power_in"))
      (node (ref "OC1") (pin "3") (pinfunction "3_3") (pintype "passive"))
      (node (ref "OC2") (pin "3") (pinfunction "3_3") (pintype "passive"))
      (node (ref "R10") (pin "1") (pinfunction "1_1") (pintype "passive"))
      (node (ref "R118") (pin "1") (pinfunction "1_1") (pintype "passive"))
      (node (ref "R119") (pin "1") (pinfunction "1_1") (pintype "passive"))
      (node (ref "R5") (pin "1") (pinfunction "1_1") (pintype "passive"))
      (node (ref "TRF1") (pin "14") (pinfunction "7_14") (pintype "passive"))
      (node (ref "TRF1") (pin "33") (pinfunction "7_33") (pintype "passive"))
      (node (ref "TRF1") (pin "48") (pinfunction "8_48") (pintype "passive"))
      (node (ref "TRF1") (pin "49") (pinfunction "7_49") (pintype "passive"))
      (node (ref "TRF1") (pin "6") (pinfunction "7_6") (pintype "passive"))
      (node (ref "Z1") (pin "1") (pinfunction "A_1") (pintype "passive"))
    )
    (net (code "21") (name "GNDA") (class "Default")
      (node (ref "C110") (pin "1") (pinfunction "1_1") (pintype "passive"))
      (node (ref "C20") (pin "-") (pinfunction "-_-") (pintype "passive"))
      (node (ref "C22") (pin "P$1") (pinfunction "1_P$1") (pintype "passive"))
      (node (ref "C23") (pin "2") (pinfunction "2_2") (pintype "passive"))
      (node (ref "C26") (pin "2") (pinfunction "2_2") (pintype "passive"))
      (node (ref "C28") (pin "1") (pinfunction "1_1") (pintype "passive"))
      (node (ref "C30") (pin "1") (pinfunction "1_1") (pintype "passive"))
      (node (ref "C31") (pin "2") (pinfunction "2_2") (pintype "passive"))
      (node (ref "C32") (pin "2") (pinfunction "2_2") (pintype "passive"))
      (node (ref "C33") (pin "1") (pinfunction "1_1") (pintype "passive"))
      (node (ref "C34") (pin "1") (pinfunction "1_1") (pintype "passive"))
      (node (ref "C35") (pin "1") (pinfunction "1_1") (pintype "passive"))
      (node (ref "C36") (pin "2") (pinfunction "2_2") (pintype "passive"))
      (node (ref "C37") (pin "2") (pinfunction "2_2") (pintype "passive"))
      (node (ref "C38") (pin "2") (pinfunction "2_2") (pintype "passive"))
      (node (ref "C39") (pin "2") (pinfunction "2_2") (pintype "passive"))
      (node (ref "C40") (pin "-") (pinfunction "-_-") (pintype "passive"))
      (node (ref "C40") (pin "-1") (pinfunction "-_-1") (pintype "passive"))
      (node (ref "C41") (pin "2") (pinfunction "2_2") (pintype "passive"))
      (node (ref "C42") (pin "-") (pinfunction "-_-") (pintype "passive"))
      (node (ref "C43") (pin "1") (pinfunction "1_1") (pintype "passive"))
      (node (ref "C44") (pin "2") (pinfunction "2_2") (pintype "passive"))
      (node (ref "C45") (pin "2") (pinfunction "2_2") (pintype "passive"))
      (node (ref "C47") (pin "2") (pinfunction "2_2") (pintype "passive"))
      (node (ref "C48") (pin "2") (pinfunction "2_2") (pintype "passive"))
      (node (ref "C49") (pin "2") (pinfunction "2_2") (pintype "passive"))
      (node (ref "C51") (pin "2") (pinfunction "2_2") (pintype "passive"))
      (node (ref "C53") (pin "2") (pinfunction "2_2") (pintype "passive"))
      (node (ref "C54") (pin "2") (pinfunction "2_2") (pintype "passive"))
      (node (ref "C55") (pin "2") (pinfunction "2_2") (pintype "passive"))
      (node (ref "C57") (pin "2") (pinfunction "2_2") (pintype "passive"))
      (node (ref "C60") (pin "1") (pinfunction "1_1") (pintype "passive"))
      (node (ref "C61") (pin "2") (pinfunction "2_2") (pintype "passive"))
      (node (ref "C62") (pin "1") (pinfunction "1_1") (pintype "passive"))
      (node (ref "C63") (pin "2") (pinfunction "2_2") (pintype "passive"))
      (node (ref "C64") (pin "2") (pinfunction "2_2") (pintype "passive"))
      (node (ref "C65") (pin "1") (pinfunction "1_1") (pintype "passive"))
      (node (ref "C66") (pin "2") (pinfunction "2_2") (pintype "passive"))
      (node (ref "C67") (pin "2") (pinfunction "2_2") (pintype "passive"))
      (node (ref "C68") (pin "1") (pinfunction "1_1") (pintype "passive"))
      (node (ref "C69") (pin "1") (pinfunction "1_1") (pintype "passive"))
      (node (ref "C70") (pin "1") (pinfunction "1_1") (pintype "passive"))
      (node (ref "C72") (pin "1") (pinfunction "1_1") (pintype "passive"))
      (node (ref "C75") (pin "P$1") (pinfunction "1_P$1") (pintype "passive"))
      (node (ref "C78") (pin "2") (pinfunction "2_2") (pintype "passive"))
      (node (ref "C79") (pin "1") (pinfunction "1_1") (pintype "passive"))
      (node (ref "C87") (pin "P$1") (pinfunction "1_P$1") (pintype "passive"))
      (node (ref "C98") (pin "1") (pinfunction "1_1") (pintype "passive"))
      (node (ref "D12") (pin "A1") (pinfunction "A1_A1") (pintype "passive"))
      (node (ref "D13") (pin "1") (pinfunction "A_1") (pintype "passive"))
      (node (ref "D18") (pin "A") (pinfunction "A_A") (pintype "passive"))
      (node (ref "H2") (pin "1") (pinfunction "P$1_1") (pintype "bidirectional"))
      (node (ref "H2") (pin "2") (pinfunction "P$1_2") (pintype "bidirectional"))
      (node (ref "H2") (pin "3") (pinfunction "P$2_3") (pintype "bidirectional"))
      (node (ref "H2") (pin "4") (pinfunction "P$2_4") (pintype "bidirectional"))
      (node (ref "IC2") (pin "5") (pinfunction "5.TRIG_5") (pintype "output"))
      (node (ref "IC2") (pin "7") (pinfunction "7.GND_7") (pintype "input"))
      (node (ref "IC4") (pin "1") (pinfunction "GND_1") (pintype "input"))
      (node (ref "IC5") (pin "4") (pinfunction "V-_4") (pintype "power_in"))
      (node (ref "IC6") (pin "A") (pinfunction "1_A") (pintype "passive"))
      (node (ref "IC9") (pin "4") (pinfunction "V-_4") (pintype "power_in"))
      (node (ref "L2") (pin "1") (pinfunction "1.GND_1") (pintype "passive"))
      (node (ref "L2") (pin "4") (pinfunction "4.GND_4") (pintype "passive"))
      (node (ref "PROG1") (pin "3") (pinfunction "GND_3") (pintype "passive"))
      (node (ref "PROG2") (pin "3") (pinfunction "GND_3") (pintype "passive"))
      (node (ref "Q2") (pin "S") (pinfunction "S_S") (pintype "passive"))
      (node (ref "R102") (pin "1") (pinfunction "1_1") (pintype "passive"))
      (node (ref "R135") (pin "1") (pinfunction "1_1") (pintype "passive"))
      (node (ref "R25") (pin "2") (pinfunction "2_2") (pintype "passive"))
      (node (ref "R26") (pin "2") (pinfunction "2_2") (pintype "passive"))
      (node (ref "R38") (pin "2") (pinfunction "2_2") (pintype "passive"))
      (node (ref "R39") (pin "2") (pinfunction "2_2") (pintype "passive"))
      (node (ref "R40") (pin "2") (pinfunction "2_2") (pintype "passive"))
      (node (ref "R41") (pin "2") (pinfunction "2_2") (pintype "passive"))
      (node (ref "R42") (pin "2") (pinfunction "2_2") (pintype "passive"))
      (node (ref "R43") (pin "2") (pinfunction "2_2") (pintype "passive"))
      (node (ref "R44") (pin "2") (pinfunction "2_2") (pintype "passive"))
      (node (ref "R47") (pin "2") (pinfunction "2_2") (pintype "passive"))
      (node (ref "R48") (pin "2") (pinfunction "2_2") (pintype "passive"))
      (node (ref "R51") (pin "2") (pinfunction "2_2") (pintype "passive"))
      (node (ref "R56") (pin "1") (pinfunction "1_1") (pintype "passive"))
      (node (ref "R58") (pin "2") (pinfunction "2_2") (pintype "passive"))
      (node (ref "R64") (pin "1") (pinfunction "1_1") (pintype "passive"))
      (node (ref "R65") (pin "1") (pinfunction "1_1") (pintype "passive"))
      (node (ref "R68") (pin "1") (pinfunction "1_1") (pintype "passive"))
      (node (ref "R73") (pin "2") (pinfunction "2_2") (pintype "passive"))
      (node (ref "R75") (pin "1") (pinfunction "1_1") (pintype "passive"))
      (node (ref "R81") (pin "2") (pinfunction "2_2") (pintype "passive"))
      (node (ref "R82") (pin "2") (pinfunction "2_2") (pintype "passive"))
      (node (ref "R87") (pin "1") (pinfunction "1_1") (pintype "passive"))
      (node (ref "R90") (pin "1") (pinfunction "1_1") (pintype "passive"))
      (node (ref "R99") (pin "1") (pinfunction "1_1") (pintype "passive"))
      (node (ref "T5") (pin "2") (pinfunction "E_2") (pintype "passive"))
      (node (ref "T6") (pin "2") (pinfunction "E_2") (pintype "passive"))
      (node (ref "TRF1") (pin "24") (pinfunction "10_24") (pintype "passive"))
      (node (ref "TRF1") (pin "27") (pinfunction "10_27") (pintype "passive"))
      (node (ref "TRF1") (pin "40") (pinfunction "9_40") (pintype "passive"))
      (node (ref "TRF1") (pin "41") (pinfunction "10_41") (pintype "passive"))
      (node (ref "TRF1") (pin "6.1") (pinfunction "9_6.1") (pintype "passive"))
      (node (ref "TRF1") (pin "6.2") (pinfunction "9_6.2") (pintype "passive"))
      (node (ref "TRF1") (pin "6.5") (pinfunction "9_6.5") (pintype "passive"))
      (node (ref "TRF1") (pin "7") (pinfunction "10_7") (pintype "passive"))
      (node (ref "TVS1") (pin "A") (pinfunction "1_A") (pintype "passive"))
      (node (ref "U1") (pin "23") (pinfunction "VSS.._23") (pintype "bidirectional"))
      (node (ref "U1") (pin "35") (pinfunction "VSS_35") (pintype "bidirectional"))
      (node (ref "U1") (pin "47") (pinfunction "VSS._47") (pintype "bidirectional"))
      (node (ref "U1") (pin "8") (pinfunction "VSSA_8") (pintype "bidirectional"))
      (node (ref "U2") (pin "2") (pinfunction "GND_2") (pintype "bidirectional"))
      (node (ref "X2") (pin "GND") (pinfunction "GND_GND") (pintype "bidirectional"))
      (node (ref "X2") (pin "SHLD1") (pinfunction "1_SHLD1") (pintype "bidirectional"))
      (node (ref "X2") (pin "SHLD2") (pinfunction "2_SHLD2") (pintype "bidirectional"))
      (node (ref "X4") (pin "1") (pinfunction "1_1") (pintype "passive"))
      (node (ref "Z4") (pin "1") (pinfunction "A_1") (pintype "passive"))
      (node (ref "Z6") (pin "1") (pinfunction "A_1") (pintype "passive"))
    )
    (net (code "22") (name "GNDIO") (class "Default")
      (node (ref "D15") (pin "C") (pinfunction "C_C") (pintype "passive"))
      (node (ref "IC8") (pin "D") (pinfunction "D5678_D") (pintype "passive"))
      (node (ref "IC8") (pin "D1") (pinfunction "D5678_D1") (pintype "passive"))
      (node (ref "IC8") (pin "D2") (pinfunction "D5678_D2") (pintype "passive"))
      (node (ref "IC8") (pin "D3") (pinfunction "D5678_D3") (pintype "passive"))
      (node (ref "IC8") (pin "P$1") (pinfunction "D5678_P$1") (pintype "passive"))
      (node (ref "IC8") (pin "P$2") (pinfunction "D5678_P$2") (pintype "passive"))
      (node (ref "IC8") (pin "P$3") (pinfunction "D5678_P$3") (pintype "passive"))
      (node (ref "R57") (pin "1") (pinfunction "1_1") (pintype "passive"))
      (node (ref "T10") (pin "E") (pinfunction "E_E") (pintype "passive"))
      (node (ref "X3") (pin "2") (pinfunction "1_2") (pintype "passive"))
    )
    (net (code "23") (name "I_OUT_ADC") (class "Default")
      (node (ref "C62") (pin "2") (pinfunction "2_2") (pintype "passive"))
      (node (ref "R83") (pin "2") (pinfunction "2_2") (pintype "passive"))
      (node (ref "U1") (pin "17") (pinfunction "PA7_17") (pintype "bidirectional"))
    )
    (net (code "24") (name "I_PWM") (class "Default")
      (node (ref "R55") (pin "2") (pinfunction "2_2") (pintype "passive"))
      (node (ref "U1") (pin "18") (pinfunction "PB0_18") (pintype "bidirectional"))
    )
    (net (code "25") (name "JTDO") (class "Default")
      (node (ref "PROG1") (pin "6") (pinfunction "PRG_SWO_6") (pintype "passive"))
      (node (ref "PROG2") (pin "6") (pinfunction "PRG_SWO_6") (pintype "passive"))
      (node (ref "U1") (pin "39") (pinfunction "PB3_39") (pintype "bidirectional"))
    )
    (net (code "26") (name "LED_B") (class "Default")
      (node (ref "R52") (pin "1") (pinfunction "1_1") (pintype "passive"))
      (node (ref "U1") (pin "41") (pinfunction "PB5_41") (pintype "bidirectional"))
    )
    (net (code "27") (name "LED_G") (class "Default")
      (node (ref "R53") (pin "1") (pinfunction "1_1") (pintype "passive"))
      (node (ref "U1") (pin "40") (pinfunction "PB4_40") (pintype "bidirectional"))
    )
    (net (code "28") (name "LED_R") (class "Default")
      (node (ref "R49") (pin "1") (pinfunction "1_1") (pintype "passive"))
      (node (ref "U1") (pin "42") (pinfunction "PB6_42") (pintype "bidirectional"))
    )
    (net (code "29") (name "NRST") (class "Default")
      (node (ref "C30") (pin "2") (pinfunction "2_2") (pintype "passive"))
      (node (ref "PROG1") (pin "5") (pinfunction "NRST_5") (pintype "passive"))
      (node (ref "PROG2") (pin "5") (pinfunction "NRST_5") (pintype "passive"))
      (node (ref "R46") (pin "2") (pinfunction "2_2") (pintype "passive"))
      (node (ref "U1") (pin "7") (pinfunction "NRST_7") (pintype "bidirectional"))
    )
    (net (code "30") (name "Net-(B1-PadAC1)") (class "Default")
      (node (ref "B1") (pin "AC1") (pinfunction "AC1_AC1") (pintype "passive"))
      (node (ref "C4") (pin "2") (pinfunction "2_2") (pintype "passive"))
      (node (ref "C83") (pin "2") (pinfunction "2_2") (pintype "passive"))
      (node (ref "C83") (pin "4") (pinfunction "2_4") (pintype "passive"))
      (node (ref "L1") (pin "4") (pinfunction "4_4") (pintype "passive"))
      (node (ref "L1") (pin "7") (pinfunction "4_7") (pintype "passive"))
    )
    (net (code "31") (name "Net-(B1-PadAC2)") (class "Default")
      (node (ref "B1") (pin "AC2") (pinfunction "AC2_AC2") (pintype "passive"))
      (node (ref "C5") (pin "1") (pinfunction "1_1") (pintype "passive"))
      (node (ref "C83") (pin "1") (pinfunction "1_1") (pintype "passive"))
      (node (ref "C83") (pin "3") (pinfunction "1_3") (pintype "passive"))
      (node (ref "L1") (pin "2") (pinfunction "2_2") (pintype "passive"))
      (node (ref "L1") (pin "6") (pinfunction "2_6") (pintype "passive"))
    )
    (net (code "32") (name "Net-(C3-1-Pad3)") (class "Default")
      (node (ref "C3") (pin "1") (pinfunction "1_1") (pintype "passive"))
      (node (ref "C3") (pin "3") (pinfunction "1_3") (pintype "passive"))
      (node (ref "C3") (pin "5") (pinfunction "1_5") (pintype "passive"))
      (node (ref "F1") (pin "1") (pinfunction "1_1") (pintype "passive"))
      (node (ref "F2") (pin "2") (pinfunction "2_2") (pintype "passive"))
      (node (ref "L3") (pin "1") (pinfunction "1_1") (pintype "passive"))
      (node (ref "R1") (pin "2") (pinfunction "2_2") (pintype "passive"))
      (node (ref "R4") (pin "2") (pinfunction "2_2") (pintype "passive"))
    )
    (net (code "33") (name "Net-(C3-2-Pad4)") (class "Default")
      (node (ref "C3") (pin "2") (pinfunction "2_2") (pintype "passive"))
      (node (ref "C3") (pin "4") (pinfunction "2_4") (pintype "passive"))
      (node (ref "C3") (pin "6") (pinfunction "2_6") (pintype "passive"))
      (node (ref "L3") (pin "2") (pinfunction "2_2") (pintype "passive"))
      (node (ref "NTC1") (pin "P$1") (pinfunction "1_P$1") (pintype "passive"))
      (node (ref "NTC1") (pin "P$4") (pinfunction "1_P$4") (pintype "passive"))
      (node (ref "R1") (pin "1") (pinfunction "1_1") (pintype "passive"))
      (node (ref "R2") (pin "1") (pinfunction "1_1") (pintype "passive"))
    )
    (net (code "34") (name "Net-(C16-Pad1)") (class "Default")
      (node (ref "C16") (pin "1") (pinfunction "1_1") (pintype "passive"))
      (node (ref "D1") (pin "C") (pinfunction "C_C") (pintype "passive"))
      (node (ref "R13") (pin "2") (pinfunction "2_2") (pintype "passive"))
    )
    (net (code "35") (name "Net-(C16-Pad2)") (class "Default")
      (node (ref "C16") (pin "2") (pinfunction "2_2") (pintype "passive"))
      (node (ref "R19") (pin "1") (pinfunction "1_1") (pintype "passive"))
    )
    (net (code "36") (name "Net-(C17-1-Pad3)") (class "Default")
      (node (ref "C17") (pin "1") (pinfunction "1_1") (pintype "passive"))
      (node (ref "C17") (pin "3") (pinfunction "1_3") (pintype "passive"))
      (node (ref "D4") (pin "A") (pinfunction "A_A") (pintype "passive"))
      (node (ref "Q1") (pin "D") (pinfunction "D_D") (pintype "passive"))
      (node (ref "TRF1") (pin "55") (pinfunction "1_55") (pintype "passive"))
      (node (ref "TRF1") (pin "56") (pinfunction "1_56") (pintype "passive"))
      (node (ref "TRF1") (pin "57") (pinfunction "1_57") (pintype "passive"))
      (node (ref "TRF1") (pin "58") (pinfunction "1_58") (pintype "passive"))
    )
    (net (code "37") (name "Net-(C17-2-Pad4)") (class "Default")
      (node (ref "C17") (pin "2") (pinfunction "2_2") (pintype "passive"))
      (node (ref "C17") (pin "4") (pinfunction "2_4") (pintype "passive"))
      (node (ref "R31") (pin "1") (pinfunction "1_1") (pintype "passive"))
    )
    (net (code "38") (name "Net-(C19-Pad1)") (class "Default")
      (node (ref "C19") (pin "1") (pinfunction "1_1") (pintype "passive"))
      (node (ref "R35") (pin "1") (pinfunction "1_1") (pintype "passive"))
    )
    (net (code "39") (name "Net-(C19-Pad2)") (class "Default")
      (node (ref "C19") (pin "2") (pinfunction "2_2") (pintype "passive"))
      (node (ref "D6") (pin "A") (pinfunction "A_A") (pintype "passive"))
      (node (ref "R22") (pin "1") (pinfunction "1_1") (pintype "passive"))
    )
    (net (code "40") (name "Net-(C21-Pad2)") (class "Default")
      (node (ref "C21") (pin "2") (pinfunction "2_2") (pintype "passive"))
      (node (ref "R25") (pin "1") (pinfunction "1_1") (pintype "passive"))
      (node (ref "R26") (pin "1") (pinfunction "1_1") (pintype "passive"))
      (node (ref "R39") (pin "1") (pinfunction "1_1") (pintype "passive"))
      (node (ref "R40") (pin "1") (pinfunction "1_1") (pintype "passive"))
      (node (ref "R41") (pin "1") (pinfunction "1_1") (pintype "passive"))
      (node (ref "R42") (pin "1") (pinfunction "1_1") (pintype "passive"))
      (node (ref "R43") (pin "1") (pinfunction "1_1") (pintype "passive"))
    )
    (net (code "41") (name "Net-(C43-Pad2)") (class "Default")
      (node (ref "C43") (pin "2") (pinfunction "2_2") (pintype "passive"))
      (node (ref "R60") (pin "2") (pinfunction "2_2") (pintype "passive"))
      (node (ref "R62") (pin "2") (pinfunction "2_2") (pintype "passive"))
    )
    (net (code "42") (name "Net-(C52-Pad1)") (class "Default")
      (node (ref "C52") (pin "1") (pinfunction "1_1") (pintype "passive"))
      (node (ref "R70") (pin "1") (pinfunction "1_1") (pintype "passive"))
    )
    (net (code "43") (name "Net-(C56-Pad1)") (class "Default")
      (node (ref "C56") (pin "1") (pinfunction "1_1") (pintype "passive"))
      (node (ref "R76") (pin "1") (pinfunction "1_1") (pintype "passive"))
    )
    (net (code "44") (name "Net-(C68-Pad2)") (class "Default")
      (node (ref "C68") (pin "2") (pinfunction "2_2") (pintype "passive"))
      (node (ref "R103") (pin "1") (pinfunction "1_1") (pintype "passive"))
      (node (ref "R104") (pin "2") (pinfunction "2_2") (pintype "passive"))
    )
    (net (code "45") (name "Net-(C77-Pad1)") (class "Default")
      (node (ref "C77") (pin "1") (pinfunction "1_1") (pintype "passive"))
      (node (ref "R194") (pin "2") (pinfunction "2_2") (pintype "passive"))
    )
    (net (code "46") (name "Net-(C84-Pad+)") (class "Default")
      (node (ref "C84") (pin "+") (pinfunction "+_+") (pintype "passive"))
      (node (ref "C84_X") (pin "+") (pinfunction "+_+") (pintype "passive"))
      (node (ref "C85") (pin "1") (pinfunction "1_1") (pintype "passive"))
      (node (ref "L4") (pin "4") (pinfunction "4_4") (pintype "passive"))
      (node (ref "X3") (pin "1") (pinfunction "1_1") (pintype "passive"))
    )
    (net (code "47") (name "Net-(C89-2-Pad4)") (class "Default")
      (node (ref "C89") (pin "2") (pinfunction "2_2") (pintype "passive"))
      (node (ref "C89") (pin "4") (pinfunction "2_4") (pintype "passive"))
      (node (ref "L1") (pin "3") (pinfunction "3_3") (pintype "passive"))
      (node (ref "L1") (pin "8") (pinfunction "3_8") (pintype "passive"))
      (node (ref "L3") (pin "4") (pinfunction "4_4") (pintype "passive"))
    )
    (net (code "48") (name "Net-(C90-1-Pad3)") (class "Default")
      (node (ref "C90") (pin "1") (pinfunction "1_1") (pintype "passive"))
      (node (ref "C90") (pin "3") (pinfunction "1_3") (pintype "passive"))
      (node (ref "L1") (pin "1") (pinfunction "1_1") (pintype "passive"))
      (node (ref "L1") (pin "5") (pinfunction "1_5") (pintype "passive"))
      (node (ref "L3") (pin "3") (pinfunction "3_3") (pintype "passive"))
    )
    (net (code "49") (name "Net-(D1-PadA)") (class "Default")
      (node (ref "D1") (pin "A") (pinfunction "A_A") (pintype "passive"))
      (node (ref "R19") (pin "2") (pinfunction "2_2") (pintype "passive"))
      (node (ref "R20") (pin "2") (pinfunction "2_2") (pintype "passive"))
    )
    (net (code "50") (name "Net-(D2-PadC)") (class "Default")
      (node (ref "D2") (pin "C") (pinfunction "C_C") (pintype "passive"))
      (node (ref "R17") (pin "1") (pinfunction "1_1") (pintype "passive"))
      (node (ref "R18") (pin "1") (pinfunction "1_1") (pintype "passive"))
    )
    (net (code "51") (name "Net-(D3-PadC)") (class "Default")
      (node (ref "D3") (pin "C") (pinfunction "C_C") (pintype "passive"))
      (node (ref "R23") (pin "1") (pinfunction "1_1") (pintype "passive"))
      (node (ref "R24") (pin "1") (pinfunction "1_1") (pintype "passive"))
    )
    (net (code "52") (name "Net-(D4-PadC)") (class "Default")
      (node (ref "D4") (pin "C") (pinfunction "C_C") (pintype "passive"))
      (node (ref "R17") (pin "2") (pinfunction "2_2") (pintype "passive"))
      (node (ref "R18") (pin "2") (pinfunction "2_2") (pintype "passive"))
      (node (ref "R23") (pin "2") (pinfunction "2_2") (pintype "passive"))
      (node (ref "R24") (pin "2") (pinfunction "2_2") (pintype "passive"))
    )
    (net (code "53") (name "Net-(D5-PadA)") (class "Default")
      (node (ref "D5") (pin "A") (pinfunction "A_A") (pintype "passive"))
      (node (ref "Q1") (pin "G") (pinfunction "G_G") (pintype "passive"))
      (node (ref "R14") (pin "1") (pinfunction "1_1") (pintype "passive"))
      (node (ref "R21") (pin "2") (pinfunction "2_2") (pintype "passive"))
    )
    (net (code "54") (name "Net-(D5-PadC)") (class "Default")
      (node (ref "D5") (pin "C") (pinfunction "C_C") (pintype "passive"))
      (node (ref "R14") (pin "2") (pinfunction "2_2") (pintype "passive"))
      (node (ref "R15") (pin "1") (pinfunction "1_1") (pintype "passive"))
    )
    (net (code "55") (name "Net-(D9-A1)") (class "Default")
      (node (ref "C64") (pin "1") (pinfunction "1_1") (pintype "passive"))
      (node (ref "D9") (pin "1") (pinfunction "A1_1") (pintype "passive"))
      (node (ref "D9") (pin "2") (pinfunction "A2_2") (pintype "passive"))
      (node (ref "R85") (pin "1") (pinfunction "1_1") (pintype "passive"))
      (node (ref "TVS1") (pin "C") (pinfunction "2_C") (pintype "passive"))
    )
    (net (code "56") (name "Net-(D11-PadA)") (class "Default")
      (node (ref "D11") (pin "A") (pinfunction "A_A") (pintype "passive"))
      (node (ref "R93") (pin "1") (pinfunction "1_1") (pintype "passive"))
    )
    (net (code "57") (name "Net-(D15-PadA)") (class "Default")
      (node (ref "D15") (pin "A") (pinfunction "A_A") (pintype "passive"))
      (node (ref "R117") (pin "2") (pinfunction "2_2") (pintype "passive"))
      (node (ref "T10") (pin "B") (pinfunction "B_B") (pintype "passive"))
    )
    (net (code "58") (name "Net-(IC1-CS)") (class "Default")
      (node (ref "C9") (pin "2") (pinfunction "2_2") (pintype "passive"))
      (node (ref "IC1") (pin "3") (pinfunction "CS_3") (pintype "input"))
      (node (ref "R6") (pin "1") (pinfunction "1_1") (pintype "passive"))
    )
    (net (code "59") (name "Net-(IC1-DRV)") (class "Default")
      (node (ref "IC1") (pin "5") (pinfunction "DRV_5") (pintype "output"))
      (node (ref "R15") (pin "2") (pinfunction "2_2") (pintype "passive"))
    )
    (net (code "60") (name "Net-(IC1-FAULT)") (class "Default")
      (node (ref "C6") (pin "1") (pinfunction "1_1") (pintype "passive"))
      (node (ref "IC1") (pin "1") (pinfunction "FAULT_1") (pintype "power_in"))
      (node (ref "R5") (pin "2") (pinfunction "2_2") (pintype "passive"))
      (node (ref "Z2") (pin "1") (pinfunction "A_1") (pintype "passive"))
    )
    (net (code "61") (name "Net-(IC1-FB)") (class "Default")
      (node (ref "C8") (pin "1") (pinfunction "1_1") (pintype "passive"))
      (node (ref "IC1") (pin "2") (pinfunction "FB_2") (pintype "input"))
      (node (ref "OC1") (pin "4") (pinfunction "4_4") (pintype "passive"))
      (node (ref "OC2") (pin "4") (pinfunction "4_4") (pintype "passive"))
    )
    (net (code "62") (name "Net-(IC1-HV)") (class "Default")
      (node (ref "IC1") (pin "8") (pinfunction "HV_8") (pintype "input"))
      (node (ref "R12") (pin "2") (pinfunction "2_2") (pintype "passive"))
    )
    (net (code "63") (name "Net-(IC1-VCC)") (class "Default")
      (node (ref "C14") (pin "1") (pinfunction "1_1") (pintype "passive"))
      (node (ref "C15") (pin "1") (pinfunction "1_1") (pintype "passive"))
      (node (ref "IC1") (pin "6") (pinfunction "VCC_6") (pintype "input"))
      (node (ref "R16") (pin "2") (pinfunction "2_2") (pintype "passive"))
      (node (ref "Z2") (pin "3") (pinfunction "C_3") (pintype "passive"))
    )
    (net (code "64") (name "Net-(IC2-2.MIN_TOFF)") (class "Default")
      (node (ref "IC2") (pin "2") (pinfunction "2.MIN_TOFF_2") (pintype "input"))
      (node (ref "R48") (pin "1") (pinfunction "1_1") (pintype "passive"))
    )
    (net (code "65") (name "Net-(IC2-3.MIN_TON)") (class "Default")
      (node (ref "IC2") (pin "3") (pinfunction "3.MIN_TON_3") (pintype "input"))
      (node (ref "R47") (pin "1") (pinfunction "1_1") (pintype "passive"))
    )
    (net (code "66") (name "Net-(IC2-8.DRV)") (class "Default")
      (node (ref "IC2") (pin "8") (pinfunction "8.DRV_8") (pintype "input"))
      (node (ref "R36") (pin "1") (pinfunction "1_1") (pintype "passive"))
    )
    (net (code "67") (name "Net-(IC3-CC+)") (class "Default")
      (node (ref "C80") (pin "2") (pinfunction "2_2") (pintype "passive"))
      (node (ref "IC3") (pin "3") (pinfunction "CC+_3") (pintype "input"))
      (node (ref "R62") (pin "1") (pinfunction "1_1") (pintype "passive"))
      (node (ref "R63") (pin "2") (pinfunction "2_2") (pintype "passive"))
    )
    (net (code "68") (name "Net-(IC3-CC-)") (class "Default")
      (node (ref "C80") (pin "1") (pinfunction "1_1") (pintype "passive"))
      (node (ref "IC3") (pin "2") (pinfunction "CC-_2") (pintype "input"))
      (node (ref "R66") (pin "1") (pinfunction "1_1") (pintype "passive"))
      (node (ref "R70") (pin "2") (pinfunction "2_2") (pintype "passive"))
    )
    (net (code "69") (name "Net-(IC3-CV-)") (class "Default")
      (node (ref "IC3") (pin "4") (pinfunction "CV-_4") (pintype "input"))
      (node (ref "R76") (pin "2") (pinfunction "2_2") (pintype "passive"))
      (node (ref "R79") (pin "1") (pinfunction "1_1") (pintype "passive"))
      (node (ref "R80") (pin "2") (pinfunction "2_2") (pintype "passive"))
    )
    (net (code "70") (name "Net-(IC3-OUT)") (class "Default")
      (node (ref "C52") (pin "2") (pinfunction "2_2") (pintype "passive"))
      (node (ref "C56") (pin "2") (pinfunction "2_2") (pintype "passive"))
      (node (ref "IC3") (pin "7") (pinfunction "OUT_7") (pintype "output"))
      (node (ref "R74") (pin "1") (pinfunction "1_1") (pintype "passive"))
    )
    (net (code "71") (name "Net-(IC3-VCC)") (class "Default")
      (node (ref "C46") (pin "2") (pinfunction "2_2") (pintype "passive"))
      (node (ref "IC3") (pin "8") (pinfunction "VCC_8") (pintype "power_in"))
      (node (ref "R69") (pin "2") (pinfunction "2_2") (pintype "passive"))
    )
    (net (code "72") (name "Net-(IC5A--IN)") (class "Default")
      (node (ref "C58") (pin "1") (pinfunction "1_1") (pintype "passive"))
      (node (ref "IC5") (pin "2") (pinfunction "-IN_2") (pintype "input"))
      (node (ref "R75") (pin "2") (pinfunction "2_2") (pintype "passive"))
      (node (ref "R77") (pin "1") (pinfunction "1_1") (pintype "passive"))
    )
    (net (code "73") (name "Net-(IC5A-OUT)") (class "Default")
      (node (ref "C58") (pin "2") (pinfunction "2_2") (pintype "passive"))
      (node (ref "IC5") (pin "1") (pinfunction "OUT_1") (pintype "output"))
      (node (ref "R77") (pin "2") (pinfunction "2_2") (pintype "passive"))
      (node (ref "R83") (pin "1") (pinfunction "1_1") (pintype "passive"))
    )
    (net (code "74") (name "Net-(IC5B-+IN)") (class "Default")
      (node (ref "C81") (pin "2") (pinfunction "2_2") (pintype "passive"))
      (node (ref "IC5") (pin "5") (pinfunction "+IN_5") (pintype "input"))
      (node (ref "R67") (pin "1") (pinfunction "1_1") (pintype "passive"))
    )
    (net (code "75") (name "Net-(IC5B--IN)") (class "Default")
      (node (ref "C50") (pin "1") (pinfunction "1_1") (pintype "passive"))
      (node (ref "C81") (pin "1") (pinfunction "1_1") (pintype "passive"))
      (node (ref "IC5") (pin "6") (pinfunction "-IN_6") (pintype "input"))
      (node (ref "R68") (pin "2") (pinfunction "2_2") (pintype "passive"))
      (node (ref "R71") (pin "1") (pinfunction "1_1") (pintype "passive"))
    )
    (net (code "76") (name "Net-(IC6-2)") (class "Default")
      (node (ref "IC6") (pin "R") (pinfunction "2_R") (pintype "passive"))
      (node (ref "R89") (pin "1") (pinfunction "1_1") (pintype "passive"))
      (node (ref "R90") (pin "2") (pinfunction "2_2") (pintype "passive"))
    )
    (net (code "77") (name "Net-(IC6-3)") (class "Default")
      (node (ref "C65") (pin "2") (pinfunction "2_2") (pintype "passive"))
      (node (ref "IC6") (pin "C") (pinfunction "3_C") (pintype "passive"))
      (node (ref "IC9") (pin "3") (pinfunction "+IN_3") (pintype "input"))
      (node (ref "R88") (pin "1") (pinfunction "1_1") (pintype "passive"))
      (node (ref "R89") (pin "2") (pinfunction "2_2") (pintype "passive"))
    )
    (net (code "78") (name "Net-(IC8-G4)") (class "Default")
      (node (ref "IC8") (pin "GATE") (pinfunction "G4_GATE") (pintype "passive"))
      (node (ref "R107") (pin "1") (pinfunction "1_1") (pintype "passive"))
      (node (ref "R116") (pin "2") (pinfunction "2_2") (pintype "passive"))
      (node (ref "T7") (pin "3") (pinfunction "C_3") (pintype "passive"))
      (node (ref "T9") (pin "3") (pinfunction "C_3") (pintype "passive"))
      (node (ref "Z8") (pin "3") (pinfunction "C_3") (pintype "passive"))
    )
    (net (code "79") (name "Net-(IC9A--IN)") (class "Default")
      (node (ref "IC9") (pin "1") (pinfunction "OUT_1") (pintype "output"))
      (node (ref "IC9") (pin "2") (pinfunction "-IN_2") (pintype "input"))
      (node (ref "R101") (pin "2") (pinfunction "2_2") (pintype "passive"))
      (node (ref "R98") (pin "2") (pinfunction "2_2") (pintype "passive"))
    )
    (net (code "80") (name "Net-(IC9B-+IN)") (class "Default")
      (node (ref "D12") (pin "A") (pinfunction "A_A") (pintype "passive"))
      (node (ref "IC9") (pin "5") (pinfunction "+IN_5") (pintype "input"))
      (node (ref "R105") (pin "1") (pinfunction "1_1") (pintype "passive"))
      (node (ref "R94") (pin "2") (pinfunction "2_2") (pintype "passive"))
      (node (ref "R98") (pin "1") (pinfunction "1_1") (pintype "passive"))
    )
    (net (code "81") (name "Net-(IC9B--IN)") (class "Default")
      (node (ref "IC9") (pin "6") (pinfunction "-IN_6") (pintype "input"))
      (node (ref "R101") (pin "1") (pinfunction "1_1") (pintype "passive"))
      (node (ref "R102") (pin "2") (pinfunction "2_2") (pintype "passive"))
      (node (ref "R106") (pin "1") (pinfunction "1_1") (pintype "passive"))
    )
    (net (code "82") (name "Net-(IC9B-OUT)") (class "Default")
      (node (ref "IC9") (pin "7") (pinfunction "OUT_7") (pintype "output"))
      (node (ref "R105") (pin "2") (pinfunction "2_2") (pintype "passive"))
      (node (ref "R106") (pin "2") (pinfunction "2_2") (pintype "passive"))
      (node (ref "R108") (pin "1") (pinfunction "1_1") (pintype "passive"))
    )
    (net (code "83") (name "Net-(L2-Pad2)") (class "Default")
      (node (ref "L2") (pin "2") (pinfunction "2_2") (pintype "passive"))
      (node (ref "X2") (pin "D+") (pinfunction "D+_D+") (pintype "bidirectional"))
    )
    (net (code "84") (name "Net-(L2-Pad3)") (class "Default")
      (node (ref "L2") (pin "3") (pinfunction "3_3") (pintype "passive"))
      (node (ref "X2") (pin "D-") (pinfunction "D-_D-") (pintype "bidirectional"))
    )
    (net (code "85") (name "Net-(L2-Pad5)") (class "Default")
      (node (ref "L2") (pin "5") (pinfunction "5_5") (pintype "passive"))
      (node (ref "R97") (pin "1") (pinfunction "1_1") (pintype "passive"))
    )
    (net (code "86") (name "Net-(L2-Pad6)") (class "Default")
      (node (ref "L2") (pin "6") (pinfunction "6_6") (pintype "passive"))
      (node (ref "R96") (pin "1") (pinfunction "1_1") (pintype "passive"))
    )
    (net (code "87") (name "Net-(L5-1)") (class "Default")
      (node (ref "C77") (pin "2") (pinfunction "2_2") (pintype "passive"))
      (node (ref "D18") (pin "C") (pinfunction "C_C") (pintype "passive"))
      (node (ref "L5") (pin "2") (pinfunction "1_2") (pintype "passive"))
      (node (ref "U2") (pin "6") (pinfunction "LX_6") (pintype "bidirectional"))
    )
    (net (code "88") (name "Net-(LED1-Pad1)") (class "Default")
      (node (ref "LED1") (pin "1") (pinfunction "1_1") (pintype "passive"))
      (node (ref "R49") (pin "2") (pinfunction "2_2") (pintype "passive"))
    )
    (net (code "89") (name "Net-(LED1-Pad3)") (class "Default")
      (node (ref "LED1") (pin "3") (pinfunction "3_3") (pintype "passive"))
      (node (ref "R53") (pin "2") (pinfunction "2_2") (pintype "passive"))
    )
    (net (code "90") (name "Net-(LED1-Pad4)") (class "Default")
      (node (ref "LED1") (pin "4") (pinfunction "4_4") (pintype "passive"))
      (node (ref "R52") (pin "2") (pinfunction "2_2") (pintype "passive"))
    )
    (net (code "91") (name "Net-(NTC1-2-PadP$2)") (class "Default")
      (node (ref "NTC1") (pin "P$2") (pinfunction "2_P$2") (pintype "passive"))
      (node (ref "NTC1") (pin "P$3") (pinfunction "2_P$3") (pintype "passive"))
      (node (ref "X1") (pin "1") (pinfunction "1_1") (pintype "passive"))
    )
    (net (code "92") (name "Net-(OC1-Pad2)") (class "Default")
      (node (ref "OC1") (pin "2") (pinfunction "2_2") (pintype "passive"))
      (node (ref "R74") (pin "2") (pinfunction "2_2") (pintype "passive"))
    )
    (net (code "93") (name "Net-(Q2-PadG)") (class "Default")
      (node (ref "Q2") (pin "G") (pinfunction "G_G") (pintype "passive"))
      (node (ref "R36") (pin "2") (pinfunction "2_2") (pintype "passive"))
      (node (ref "R38") (pin "1") (pinfunction "1_1") (pintype "passive"))
    )
    (net (code "94") (name "Net-(R2-Pad2)") (class "Default")
      (node (ref "R2") (pin "2") (pinfunction "2_2") (pintype "passive"))
      (node (ref "R3") (pin "2") (pinfunction "2_2") (pintype "passive"))
    )
    (net (code "95") (name "Net-(R3-Pad1)") (class "Default")
      (node (ref "R3") (pin "1") (pinfunction "1_1") (pintype "passive"))
      (node (ref "R4") (pin "1") (pinfunction "1_1") (pintype "passive"))
    )
    (net (code "96") (name "Net-(R7-Pad2)") (class "Default")
      (node (ref "R7") (pin "2") (pinfunction "2_2") (pintype "passive"))
      (node (ref "R8") (pin "1") (pinfunction "1_1") (pintype "passive"))
    )
    (net (code "97") (name "Net-(R10-Pad2)") (class "Default")
      (node (ref "R10") (pin "2") (pinfunction "2_2") (pintype "passive"))
      (node (ref "R9") (pin "1") (pinfunction "1_1") (pintype "passive"))
    )
    (net (code "98") (name "Net-(R11-Pad1)") (class "Default")
      (node (ref "R11") (pin "1") (pinfunction "1_1") (pintype "passive"))
      (node (ref "R12") (pin "1") (pinfunction "1_1") (pintype "passive"))
    )
    (net (code "99") (name "Net-(R20-Pad1)") (class "Default")
      (node (ref "R20") (pin "1") (pinfunction "1_1") (pintype "passive"))
      (node (ref "TRF1") (pin "15") (pinfunction "6_15") (pintype "passive"))
      (node (ref "TRF1") (pin "34") (pinfunction "6_34") (pintype "passive"))
      (node (ref "TRF1") (pin "5") (pinfunction "6_5") (pintype "passive"))
      (node (ref "TRF1") (pin "50") (pinfunction "6_50") (pintype "passive"))
    )
    (net (code "100") (name "Net-(R22-Pad2)") (class "Default")
      (node (ref "R22") (pin "2") (pinfunction "2_2") (pintype "passive"))
      (node (ref "TRF1") (pin "23") (pinfunction "11_23") (pintype "passive"))
      (node (ref "TRF1") (pin "28") (pinfunction "11_28") (pintype "passive"))
      (node (ref "TRF1") (pin "42") (pinfunction "11_42") (pintype "passive"))
      (node (ref "TRF1") (pin "8") (pinfunction "11_8") (pintype "passive"))
    )
    (net (code "101") (name "Net-(R27-Pad2)") (class "Default")
      (node (ref "R27") (pin "2") (pinfunction "2_2") (pintype "passive"))
      (node (ref "R30") (pin "1") (pinfunction "1_1") (pintype "passive"))
    )
    (net (code "102") (name "Net-(R30-Pad2)") (class "Default")
      (node (ref "R30") (pin "2") (pinfunction "2_2") (pintype "passive"))
      (node (ref "R33") (pin "1") (pinfunction "1_1") (pintype "passive"))
      (node (ref "R34") (pin "1") (pinfunction "1_1") (pintype "passive"))
    )
    (net (code "103") (name "Net-(R31-Pad2)") (class "Default")
      (node (ref "R31") (pin "2") (pinfunction "2_2") (pintype "passive"))
      (node (ref "R33") (pin "2") (pinfunction "2_2") (pintype "passive"))
      (node (ref "R34") (pin "2") (pinfunction "2_2") (pintype "passive"))
    )
    (net (code "104") (name "Net-(R54-Pad1)") (class "Default")
      (node (ref "R54") (pin "1") (pinfunction "1_1") (pintype "passive"))
      (node (ref "R59") (pin "2") (pinfunction "2_2") (pintype "passive"))
      (node (ref "R61") (pin "1") (pinfunction "1_1") (pintype "passive"))
      (node (ref "T3") (pin "E") (pinfunction "E_E") (pintype "passive"))
    )
    (net (code "105") (name "Net-(R54-Pad2)") (class "Default")
      (node (ref "R54") (pin "2") (pinfunction "2_2") (pintype "passive"))
      (node (ref "R55") (pin "1") (pinfunction "1_1") (pintype "passive"))
      (node (ref "T3") (pin "B") (pinfunction "B_B") (pintype "passive"))
    )
    (net (code "106") (name "Net-(R59-Pad1)") (class "Default")
      (node (ref "R59") (pin "1") (pinfunction "1_1") (pintype "passive"))
      (node (ref "R60") (pin "1") (pinfunction "1_1") (pintype "passive"))
      (node (ref "T3") (pin "C") (pinfunction "C_C") (pintype "passive"))
    )
    (net (code "107") (name "Net-(R63-Pad1)") (class "Default")
      (node (ref "R63") (pin "1") (pinfunction "1_1") (pintype "passive"))
      (node (ref "R64") (pin "2") (pinfunction "2_2") (pintype "passive"))
    )
    (net (code "108") (name "Net-(R85-Pad2)") (class "Default")
      (node (ref "R85") (pin "2") (pinfunction "2_2") (pintype "passive"))
      (node (ref "X2") (pin "VBUS") (pinfunction "VBUS_VBUS") (pintype "bidirectional"))
    )
    (net (code "109") (name "Net-(R112-Pad1)") (class "Default")
      (node (ref "R112") (pin "1") (pinfunction "1_1") (pintype "passive"))
      (node (ref "R115") (pin "1") (pinfunction "1_1") (pintype "passive"))
    )
    (net (code "110") (name "Net-(R115-Pad2)") (class "Default")
      (node (ref "R115") (pin "2") (pinfunction "2_2") (pintype "passive"))
      (node (ref "T10") (pin "C") (pinfunction "C_C") (pintype "passive"))
    )
    (net (code "111") (name "Net-(R133-Pad1)") (class "Default")
      (node (ref "R133") (pin "1") (pinfunction "1_1") (pintype "passive"))
      (node (ref "R134") (pin "2") (pinfunction "2_2") (pintype "passive"))
    )
    (net (code "112") (name "Net-(T1-B)") (class "Default")
      (node (ref "R7") (pin "1") (pinfunction "1_1") (pintype "passive"))
      (node (ref "T1") (pin "1") (pinfunction "B_1") (pintype "passive"))
      (node (ref "T1_X") (pin "1") (pinfunction "B_1") (pintype "passive"))
      (node (ref "Z1") (pin "3") (pinfunction "C_3") (pintype "passive"))
    )
    (net (code "113") (name "Net-(T1-C)") (class "Default")
      (node (ref "C13") (pin "+") (pinfunction "+_+") (pintype "passive"))
      (node (ref "C29") (pin "2") (pinfunction "2_2") (pintype "passive"))
      (node (ref "R13") (pin "1") (pinfunction "1_1") (pintype "passive"))
      (node (ref "R8") (pin "2") (pinfunction "2_2") (pintype "passive"))
      (node (ref "T1") (pin "4") (pinfunction "C_4") (pintype "passive"))
      (node (ref "T1_X") (pin "3") (pinfunction "C_3") (pintype "passive"))
    )
    (net (code "114") (name "Net-(T1-E)") (class "Default")
      (node (ref "C10") (pin "+") (pinfunction "+_+") (pintype "passive"))
      (node (ref "R16") (pin "1") (pinfunction "1_1") (pintype "passive"))
      (node (ref "T1") (pin "3") (pinfunction "E_3") (pintype "passive"))
      (node (ref "T1_X") (pin "2") (pinfunction "E_2") (pintype "passive"))
    )
    (net (code "115") (name "Net-(T4-B)") (class "Default")
      (node (ref "C60") (pin "2") (pinfunction "2_2") (pintype "passive"))
      (node (ref "R82") (pin "1") (pinfunction "1_1") (pintype "passive"))
      (node (ref "R84") (pin "2") (pinfunction "2_2") (pintype "passive"))
      (node (ref "T4") (pin "1") (pinfunction "B_1") (pintype "passive"))
    )
    (net (code "116") (name "Net-(T4-C)") (class "Default")
      (node (ref "R78") (pin "1") (pinfunction "1_1") (pintype "passive"))
      (node (ref "R79") (pin "2") (pinfunction "2_2") (pintype "passive"))
      (node (ref "T4") (pin "3") (pinfunction "C_3") (pintype "passive"))
    )
    (net (code "117") (name "Net-(T4-E)") (class "Default")
      (node (ref "R81") (pin "1") (pinfunction "1_1") (pintype "passive"))
      (node (ref "T4") (pin "2") (pinfunction "E_2") (pintype "passive"))
    )
    (net (code "118") (name "Net-(T5-B)") (class "Default")
      (node (ref "R86") (pin "1") (pinfunction "1_1") (pintype "passive"))
      (node (ref "R87") (pin "2") (pinfunction "2_2") (pintype "passive"))
      (node (ref "T5") (pin "1") (pinfunction "B_1") (pintype "passive"))
    )
    (net (code "119") (name "Net-(T5-C)") (class "Default")
      (node (ref "D10") (pin "A") (pinfunction "A_A") (pintype "passive"))
      (node (ref "RL1") (pin "1") (pinfunction "1_1") (pintype "passive"))
      (node (ref "T5") (pin "3") (pinfunction "C_3") (pintype "passive"))
    )
    (net (code "120") (name "Net-(T6-B)") (class "Default")
      (node (ref "R95") (pin "1") (pinfunction "1_1") (pintype "passive"))
      (node (ref "R99") (pin "2") (pinfunction "2_2") (pintype "passive"))
      (node (ref "T6") (pin "1") (pinfunction "B_1") (pintype "passive"))
    )
    (net (code "121") (name "Net-(T6-C)") (class "Default")
      (node (ref "R104") (pin "1") (pinfunction "1_1") (pintype "passive"))
      (node (ref "T6") (pin "3") (pinfunction "C_3") (pintype "passive"))
      (node (ref "Z6") (pin "3") (pinfunction "C_3") (pintype "passive"))
    )
    (net (code "122") (name "Net-(T7-B)") (class "Default")
      (node (ref "R109") (pin "1") (pinfunction "1_1") (pintype "passive"))
      (node (ref "T7") (pin "1") (pinfunction "B_1") (pintype "passive"))
    )
    (net (code "123") (name "Net-(T9-B)") (class "Default")
      (node (ref "R113") (pin "1") (pinfunction "1_1") (pintype "passive"))
      (node (ref "R114") (pin "1") (pinfunction "1_1") (pintype "passive"))
      (node (ref "T9") (pin "1") (pinfunction "B_1") (pintype "passive"))
    )
    (net (code "124") (name "Net-(TRF1-2-Pad1)") (class "Default")
      (node (ref "TRF1") (pin "1") (pinfunction "2_1") (pintype "passive"))
      (node (ref "TRF1") (pin "17") (pinfunction "3_17") (pintype "passive"))
      (node (ref "TRF1") (pin "18") (pinfunction "2_18") (pintype "passive"))
      (node (ref "TRF1") (pin "2") (pinfunction "3_2") (pintype "passive"))
      (node (ref "TRF1") (pin "36") (pinfunction "3_36") (pintype "passive"))
      (node (ref "TRF1") (pin "37") (pinfunction "2_37") (pintype "passive"))
      (node (ref "TRF1") (pin "53") (pinfunction "3_53") (pintype "passive"))
      (node (ref "TRF1") (pin "54") (pinfunction "2_54") (pintype "passive"))
    )
    (net (code "125") (name "Net-(U1-BOOT0)") (class "Default")
      (node (ref "R56") (pin "2") (pinfunction "2_2") (pintype "passive"))
      (node (ref "U1") (pin "44") (pinfunction "BOOT0_44") (pintype "bidirectional"))
    )
    (net (code "126") (name "Net-(U1-PB15)") (class "Default")
      (node (ref "TP4") (pin "TP") (pinfunction "TP_TP") (pintype "input"))
      (node (ref "U1") (pin "28") (pinfunction "PB15_28") (pintype "bidirectional"))
    )
    (net (code "127") (name "Net-(U1-VDDA)") (class "Default")
      (node (ref "C31") (pin "1") (pinfunction "1_1") (pintype "passive"))
      (node (ref "C32") (pin "1") (pinfunction "1_1") (pintype "passive"))
      (node (ref "R45") (pin "1") (pinfunction "1_1") (pintype "passive"))
      (node (ref "U1") (pin "9") (pinfunction "VDDA_9") (pintype "bidirectional"))
    )
    (net (code "128") (name "Net-(U2-BS)") (class "Default")
      (node (ref "R194") (pin "1") (pinfunction "1_1") (pintype "passive"))
      (node (ref "U2") (pin "1") (pinfunction "BS_1") (pintype "bidirectional"))
    )
    (net (code "129") (name "Net-(U2-EN)") (class "Default")
      (node (ref "R193") (pin "1") (pinfunction "1_1") (pintype "passive"))
      (node (ref "U2") (pin "4") (pinfunction "EN_4") (pintype "bidirectional"))
    )
    (net (code "130") (name "Net-(X1B-1)") (class "Default")
      (node (ref "F1") (pin "2") (pinfunction "2_2") (pintype "passive"))
      (node (ref "F2") (pin "1") (pinfunction "1_1") (pintype "passive"))
      (node (ref "X1") (pin "2") (pinfunction "1_2") (pintype "passive"))
    )
    (net (code "131") (name "Net-(X3C-1)") (class "Default")
      (node (ref "RL1") (pin "P0") (pinfunction "P0_P0") (pintype "passive"))
      (node (ref "RL1") (pin "P1") (pinfunction "P1_P1") (pintype "passive"))
      (node (ref "X3") (pin "3") (pinfunction "1_3") (pintype "passive"))
    )
    (net (code "132") (name "Net-(X3D-1)") (class "Default")
      (node (ref "RL1") (pin "S0") (pinfunction "S0_S0") (pintype "passive"))
      (node (ref "X3") (pin "4") (pinfunction "1_4") (pintype "passive"))
    )
    (net (code "133") (name "Net-(X4B-1)") (class "Default")
      (node (ref "R94") (pin "1") (pinfunction "1_1") (pintype "passive"))
      (node (ref "X4") (pin "2") (pinfunction "1_2") (pintype "passive"))
    )
    (net (code "134") (name "Net-(X4C-1)") (class "Default")
      (node (ref "D11") (pin "C") (pinfunction "C_C") (pintype "passive"))
      (node (ref "X4") (pin "3") (pinfunction "1_3") (pintype "passive"))
    )
    (net (code "135") (name "Net-(Z4-C)") (class "Default")
      (node (ref "R91") (pin "2") (pinfunction "2_2") (pintype "passive"))
      (node (ref "R92") (pin "2") (pinfunction "2_2") (pintype "passive"))
      (node (ref "R93") (pin "2") (pinfunction "2_2") (pintype "passive"))
      (node (ref "Z4") (pin "3") (pinfunction "C_3") (pintype "passive"))
    )
    (net (code "136") (name "Net-(Z5-A)") (class "Default")
      (node (ref "R103") (pin "2") (pinfunction "2_2") (pintype "passive"))
      (node (ref "Z5") (pin "1") (pinfunction "A_1") (pintype "passive"))
    )
    (net (code "137") (name "Net-(Z5-C)") (class "Default")
      (node (ref "OC2") (pin "2") (pinfunction "2_2") (pintype "passive"))
      (node (ref "Z5") (pin "3") (pinfunction "C_3") (pintype "passive"))
    )
    (net (code "138") (name "Net-(Z7-C)") (class "Default")
      (node (ref "D14") (pin "C") (pinfunction "C_C") (pintype "passive"))
      (node (ref "R112") (pin "2") (pinfunction "2_2") (pintype "passive"))
      (node (ref "R113") (pin "2") (pinfunction "2_2") (pintype "passive"))
      (node (ref "Z7") (pin "3") (pinfunction "C_3") (pintype "passive"))
    )
    (net (code "139") (name "OVER_VOLT") (class "Default")
      (node (ref "R95") (pin "2") (pinfunction "2_2") (pintype "passive"))
      (node (ref "U1") (pin "38") (pinfunction "PA15_38") (pintype "bidirectional"))
    )
    (net (code "140") (name "PT100_ADC") (class "Default")
      (node (ref "C70") (pin "2") (pinfunction "2_2") (pintype "passive"))
      (node (ref "D13") (pin "3") (pinfunction "AC_3") (pintype "passive"))
      (node (ref "R108") (pin "2") (pinfunction "2_2") (pintype "passive"))
      (node (ref "U1") (pin "11") (pinfunction "PA1_11") (pintype "bidirectional"))
    )
    (net (code "141") (name "RELAY_OP") (class "Default")
      (node (ref "R86") (pin "2") (pinfunction "2_2") (pintype "passive"))
      (node (ref "U1") (pin "12") (pinfunction "PA2_12") (pintype "bidirectional"))
    )
    (net (code "142") (name "SWCLK") (class "Default")
      (node (ref "PROG1") (pin "2") (pinfunction "PRG_SWCLK_2") (pintype "passive"))
      (node (ref "PROG2") (pin "2") (pinfunction "PRG_SWCLK_2") (pintype "passive"))
      (node (ref "U1") (pin "37") (pinfunction "PA14_37") (pintype "bidirectional"))
    )
    (net (code "143") (name "SWDIO") (class "Default")
      (node (ref "PROG1") (pin "4") (pinfunction "PRG_SWDIO_4") (pintype "passive"))
      (node (ref "PROG2") (pin "4") (pinfunction "PRG_SWDIO_4") (pintype "passive"))
      (node (ref "U1") (pin "34") (pinfunction "PA13_34") (pintype "bidirectional"))
    )
    (net (code "144") (name "USB_DM") (class "Default")
      (node (ref "C66") (pin "1") (pinfunction "1_1") (pintype "passive"))
      (node (ref "R97") (pin "2") (pinfunction "2_2") (pintype "passive"))
      (node (ref "U1") (pin "32") (pinfunction "PA11_32") (pintype "bidirectional"))
    )
    (net (code "145") (name "USB_DP") (class "Default")
      (node (ref "C67") (pin "1") (pinfunction "1_1") (pintype "passive"))
      (node (ref "R100") (pin "1") (pinfunction "1_1") (pintype "passive"))
      (node (ref "R96") (pin "2") (pinfunction "2_2") (pintype "passive"))
      (node (ref "U1") (pin "33") (pinfunction "PA12_33") (pintype "bidirectional"))
    )
    (net (code "146") (name "VBAT_ADC") (class "Default")
      (node (ref "C44") (pin "1") (pinfunction "1_1") (pintype "passive"))
      (node (ref "R57") (pin "2") (pinfunction "2_2") (pintype "passive"))
      (node (ref "R58") (pin "1") (pinfunction "1_1") (pintype "passive"))
      (node (ref "U1") (pin "13") (pinfunction "PA3_13") (pintype "bidirectional"))
    )
    (net (code "147") (name "VOUT+_ADC") (class "Default")
      (node (ref "C41") (pin "1") (pinfunction "1_1") (pintype "passive"))
      (node (ref "R50") (pin "2") (pinfunction "2_2") (pintype "passive"))
      (node (ref "R51") (pin "1") (pinfunction "1_1") (pintype "passive"))
      (node (ref "U1") (pin "14") (pinfunction "PA4_14") (pintype "bidirectional"))
    )
    (net (code "148") (name "V_NTC_ADC") (class "Default")
      (node (ref "C53") (pin "1") (pinfunction "1_1") (pintype "passive"))
      (node (ref "R72") (pin "1") (pinfunction "1_1") (pintype "passive"))
      (node (ref "R73") (pin "1") (pinfunction "1_1") (pintype "passive"))
      (node (ref "U1") (pin "10") (pinfunction "PA0_10") (pintype "bidirectional"))
    )
    (net (code "149") (name "V_PWM") (class "Default")
      (node (ref "R84") (pin "1") (pinfunction "1_1") (pintype "passive"))
      (node (ref "U1") (pin "19") (pinfunction "PB1_19") (pintype "bidirectional"))
    )
    (net (code "150") (name "unconnected-(U1-PA8-Pad29)") (class "Default")
      (node (ref "U1") (pin "29") (pinfunction "PA8_29") (pintype "bidirectional"))
    )
    (net (code "151") (name "unconnected-(U1-PA9-Pad30)") (class "Default")
      (node (ref "U1") (pin "30") (pinfunction "PA9_30") (pintype "bidirectional"))
    )
    (net (code "152") (name "unconnected-(U1-PA10-Pad31)") (class "Default")
      (node (ref "U1") (pin "31") (pinfunction "PA10_31") (pintype "bidirectional"))
    )
    (net (code "153") (name "unconnected-(U1-PB2-Pad20)") (class "Default")
      (node (ref "U1") (pin "20") (pinfunction "PB2_20") (pintype "bidirectional"))
    )
    (net (code "154") (name "unconnected-(U1-PB7-Pad43)") (class "Default")
      (node (ref "U1") (pin "43") (pinfunction "PB7_43") (pintype "bidirectional"))
    )
    (net (code "155") (name "unconnected-(U1-PB8-Pad45)") (class "Default")
      (node (ref "U1") (pin "45") (pinfunction "PB8_45") (pintype "bidirectional"))
    )
    (net (code "156") (name "unconnected-(U1-PB9-Pad46)") (class "Default")
      (node (ref "U1") (pin "46") (pinfunction "PB9_46") (pintype "bidirectional"))
    )
    (net (code "157") (name "unconnected-(U1-PB10-Pad21)") (class "Default")
      (node (ref "U1") (pin "21") (pinfunction "PB10_21") (pintype "bidirectional"))
    )
    (net (code "158") (name "unconnected-(U1-PB11-Pad22)") (class "Default")
      (node (ref "U1") (pin "22") (pinfunction "PB11_22") (pintype "bidirectional"))
    )
    (net (code "159") (name "unconnected-(U1-PB12-Pad25)") (class "Default")
      (node (ref "U1") (pin "25") (pinfunction "PB12_25") (pintype "bidirectional"))
    )
    (net (code "160") (name "unconnected-(U1-PB13-Pad26)") (class "Default")
      (node (ref "U1") (pin "26") (pinfunction "PB13_26") (pintype "bidirectional"))
    )
    (net (code "161") (name "unconnected-(U1-PB14-Pad27)") (class "Default")
      (node (ref "U1") (pin "27") (pinfunction "PB14_27") (pintype "bidirectional"))
    )
    (net (code "162") (name "unconnected-(U1-PC13-Pad2)") (class "Default")
      (node (ref "U1") (pin "2") (pinfunction "PC13_2") (pintype "bidirectional"))
    )
    (net (code "163") (name "unconnected-(U1-PC14{slash}OSC32_IN-Pad3)") (class "Default")
      (node (ref "U1") (pin "3") (pinfunction "PC14/OSC32_IN_3") (pintype "bidirectional"))
    )
    (net (code "164") (name "unconnected-(U1-PC15{slash}OSC32_OUT-Pad4)") (class "Default")
      (node (ref "U1") (pin "4") (pinfunction "PC15/OSC32_OUT_4") (pintype "bidirectional"))
    )
    (net (code "165") (name "unconnected-(U1-VBAT-Pad1)") (class "Default")
      (node (ref "U1") (pin "1") (pinfunction "VBAT_1") (pintype "bidirectional"))
    )
  )
)
